# PGTNX01_teensy.net
KiCad netlist of a schematic drawn in EAGLE
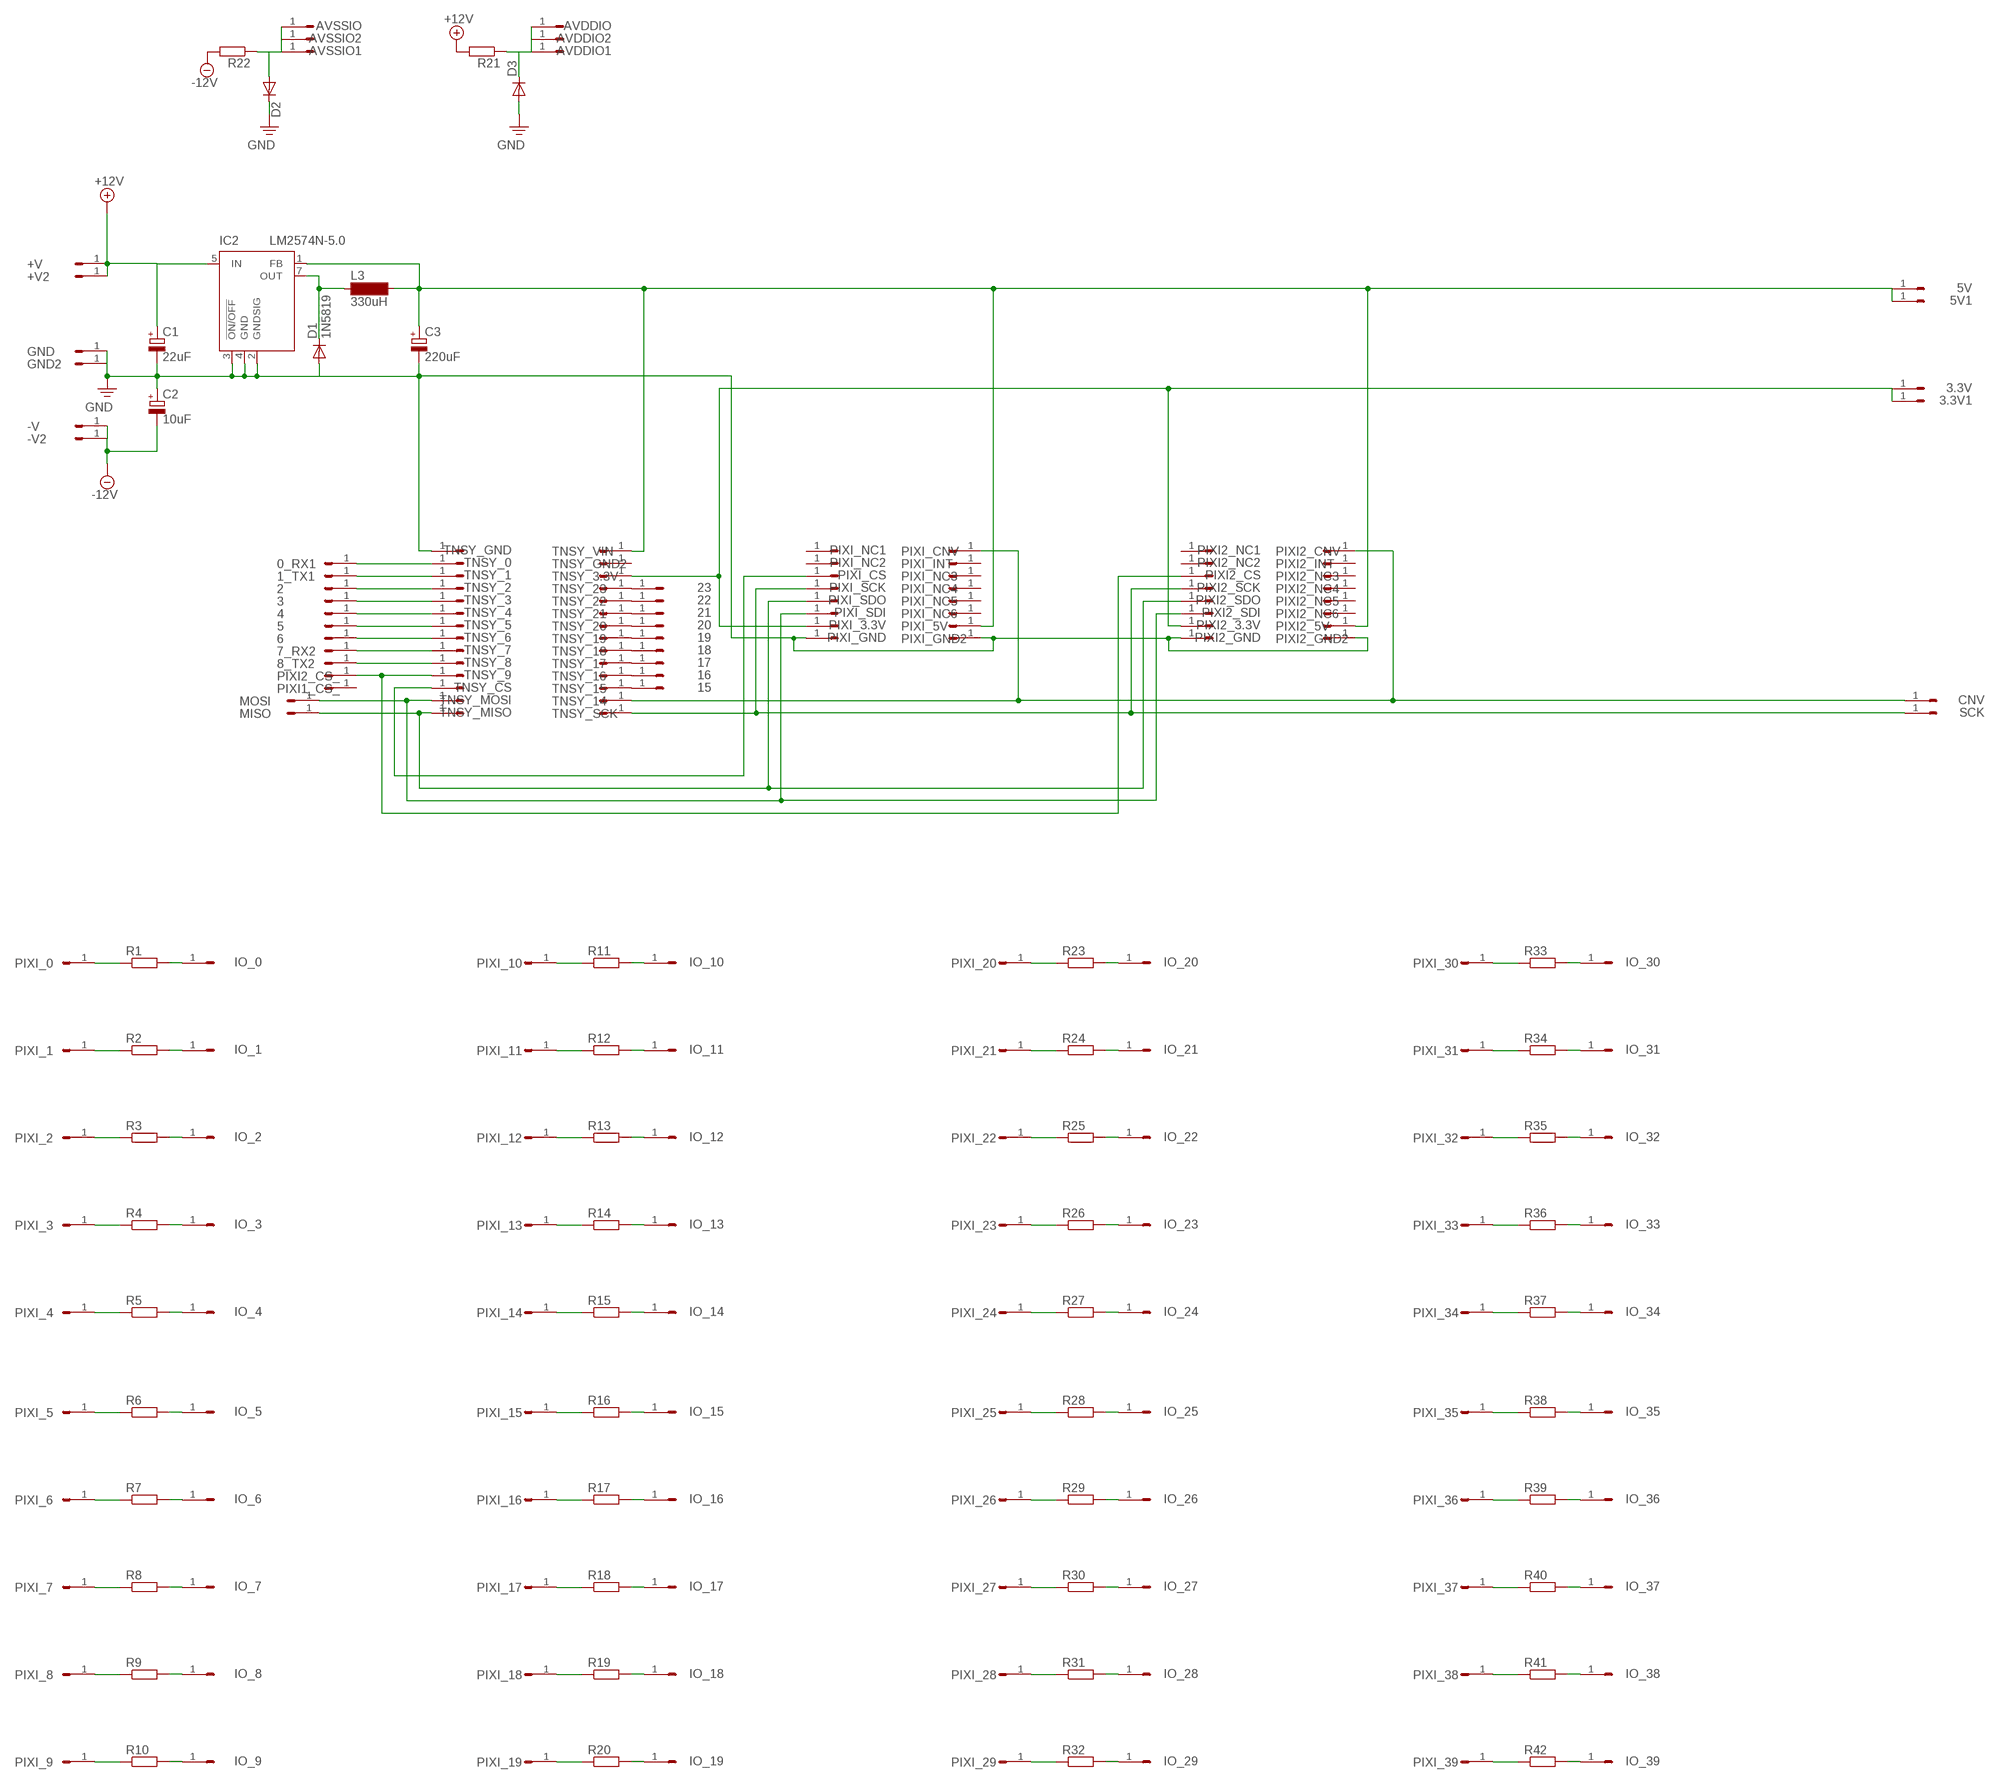
[diagram p0: schematic, sheet 1]

(export (version "E")
  (design (tool "Eeschema 10.0.6"))
  (components
    (comp (ref "+V")
      (value "HEADER/MALE/01")
      (footprint "eagle-import:HEADER_MALE_01")
      (fields (field (name "SPICEPREFIX") "X"))
      (libsource (lib "eagle-import") (part "HEADER/MALE/01"))
    )
    (comp (ref "+V2")
      (value "HEADER/MALE/01")
      (footprint "eagle-import:HEADER_MALE_01")
      (fields (field (name "SPICEPREFIX") "X"))
      (libsource (lib "eagle-import") (part "HEADER/MALE/01"))
    )
    (comp (ref "-V")
      (value "HEADER/MALE/01")
      (footprint "eagle-import:HEADER_MALE_01")
      (fields (field (name "SPICEPREFIX") "X"))
      (libsource (lib "eagle-import") (part "HEADER/MALE/01"))
    )
    (comp (ref "-V2")
      (value "HEADER/MALE/01")
      (footprint "eagle-import:HEADER_MALE_01")
      (fields (field (name "SPICEPREFIX") "X"))
      (libsource (lib "eagle-import") (part "HEADER/MALE/01"))
    )
    (comp (ref "0_RX1")
      (value "HEADER/MALE/01")
      (footprint "eagle-import:HEADER_MALE_01")
      (fields (field (name "SPICEPREFIX") "X"))
      (libsource (lib "eagle-import") (part "HEADER/MALE/01"))
    )
    (comp (ref "1_TX1")
      (value "HEADER/MALE/01")
      (footprint "eagle-import:HEADER_MALE_01")
      (fields (field (name "SPICEPREFIX") "X"))
      (libsource (lib "eagle-import") (part "HEADER/MALE/01"))
    )
    (comp (ref "2")
      (value "HEADER/MALE/01")
      (footprint "eagle-import:HEADER_MALE_01")
      (fields (field (name "SPICEPREFIX") "X"))
      (libsource (lib "eagle-import") (part "HEADER/MALE/01"))
    )
    (comp (ref "3")
      (value "HEADER/MALE/01")
      (footprint "eagle-import:HEADER_MALE_01")
      (fields (field (name "SPICEPREFIX") "X"))
      (libsource (lib "eagle-import") (part "HEADER/MALE/01"))
    )
    (comp (ref "3.3V")
      (value "HEADER/MALE/01")
      (footprint "eagle-import:HEADER_MALE_01")
      (fields (field (name "SPICEPREFIX") "X"))
      (libsource (lib "eagle-import") (part "HEADER/MALE/01"))
    )
    (comp (ref "3.3V1")
      (value "HEADER/MALE/01")
      (footprint "eagle-import:HEADER_MALE_01")
      (fields (field (name "SPICEPREFIX") "X"))
      (libsource (lib "eagle-import") (part "HEADER/MALE/01"))
    )
    (comp (ref "4")
      (value "HEADER/MALE/01")
      (footprint "eagle-import:HEADER_MALE_01")
      (fields (field (name "SPICEPREFIX") "X"))
      (libsource (lib "eagle-import") (part "HEADER/MALE/01"))
    )
    (comp (ref "5")
      (value "HEADER/MALE/01")
      (footprint "eagle-import:HEADER_MALE_01")
      (fields (field (name "SPICEPREFIX") "X"))
      (libsource (lib "eagle-import") (part "HEADER/MALE/01"))
    )
    (comp (ref "5V")
      (value "HEADER/MALE/01")
      (footprint "eagle-import:HEADER_MALE_01")
      (fields (field (name "SPICEPREFIX") "X"))
      (libsource (lib "eagle-import") (part "HEADER/MALE/01"))
    )
    (comp (ref "5V1")
      (value "HEADER/MALE/01")
      (footprint "eagle-import:HEADER_MALE_01")
      (fields (field (name "SPICEPREFIX") "X"))
      (libsource (lib "eagle-import") (part "HEADER/MALE/01"))
    )
    (comp (ref "6")
      (value "HEADER/MALE/01")
      (footprint "eagle-import:HEADER_MALE_01")
      (fields (field (name "SPICEPREFIX") "X"))
      (libsource (lib "eagle-import") (part "HEADER/MALE/01"))
    )
    (comp (ref "7_RX2")
      (value "HEADER/MALE/01")
      (footprint "eagle-import:HEADER_MALE_01")
      (fields (field (name "SPICEPREFIX") "X"))
      (libsource (lib "eagle-import") (part "HEADER/MALE/01"))
    )
    (comp (ref "8_TX2")
      (value "HEADER/MALE/01")
      (footprint "eagle-import:HEADER_MALE_01")
      (fields (field (name "SPICEPREFIX") "X"))
      (libsource (lib "eagle-import") (part "HEADER/MALE/01"))
    )
    (comp (ref "15")
      (value "HEADER/MALE/01")
      (footprint "eagle-import:HEADER_MALE_01")
      (fields (field (name "SPICEPREFIX") "X"))
      (libsource (lib "eagle-import") (part "HEADER/MALE/01"))
    )
    (comp (ref "16")
      (value "HEADER/MALE/01")
      (footprint "eagle-import:HEADER_MALE_01")
      (fields (field (name "SPICEPREFIX") "X"))
      (libsource (lib "eagle-import") (part "HEADER/MALE/01"))
    )
    (comp (ref "17")
      (value "HEADER/MALE/01")
      (footprint "eagle-import:HEADER_MALE_01")
      (fields (field (name "SPICEPREFIX") "X"))
      (libsource (lib "eagle-import") (part "HEADER/MALE/01"))
    )
    (comp (ref "18")
      (value "HEADER/MALE/01")
      (footprint "eagle-import:HEADER_MALE_01")
      (fields (field (name "SPICEPREFIX") "X"))
      (libsource (lib "eagle-import") (part "HEADER/MALE/01"))
    )
    (comp (ref "19")
      (value "HEADER/MALE/01")
      (footprint "eagle-import:HEADER_MALE_01")
      (fields (field (name "SPICEPREFIX") "X"))
      (libsource (lib "eagle-import") (part "HEADER/MALE/01"))
    )
    (comp (ref "20")
      (value "HEADER/MALE/01")
      (footprint "eagle-import:HEADER_MALE_01")
      (fields (field (name "SPICEPREFIX") "X"))
      (libsource (lib "eagle-import") (part "HEADER/MALE/01"))
    )
    (comp (ref "21")
      (value "HEADER/MALE/01")
      (footprint "eagle-import:HEADER_MALE_01")
      (fields (field (name "SPICEPREFIX") "X"))
      (libsource (lib "eagle-import") (part "HEADER/MALE/01"))
    )
    (comp (ref "22")
      (value "HEADER/MALE/01")
      (footprint "eagle-import:HEADER_MALE_01")
      (fields (field (name "SPICEPREFIX") "X"))
      (libsource (lib "eagle-import") (part "HEADER/MALE/01"))
    )
    (comp (ref "23")
      (value "HEADER/MALE/01")
      (footprint "eagle-import:HEADER_MALE_01")
      (fields (field (name "SPICEPREFIX") "X"))
      (libsource (lib "eagle-import") (part "HEADER/MALE/01"))
    )
    (comp (ref "AVDDIO")
      (value "HEADER/MALE/01")
      (footprint "eagle-import:HEADER_MALE_01")
      (fields (field (name "SPICEPREFIX") "X"))
      (libsource (lib "eagle-import") (part "HEADER/MALE/01"))
    )
    (comp (ref "AVDDIO1")
      (value "HEADER/MALE/01")
      (footprint "eagle-import:HEADER_MALE_01")
      (fields (field (name "SPICEPREFIX") "X"))
      (libsource (lib "eagle-import") (part "HEADER/MALE/01"))
    )
    (comp (ref "AVDDIO2")
      (value "HEADER/MALE/01")
      (footprint "eagle-import:HEADER_MALE_01")
      (fields (field (name "SPICEPREFIX") "X"))
      (libsource (lib "eagle-import") (part "HEADER/MALE/01"))
    )
    (comp (ref "AVSSIO")
      (value "HEADER/MALE/01")
      (footprint "eagle-import:HEADER_MALE_01")
      (fields (field (name "SPICEPREFIX") "X"))
      (libsource (lib "eagle-import") (part "HEADER/MALE/01"))
    )
    (comp (ref "AVSSIO1")
      (value "HEADER/MALE/01")
      (footprint "eagle-import:HEADER_MALE_01")
      (fields (field (name "SPICEPREFIX") "X"))
      (libsource (lib "eagle-import") (part "HEADER/MALE/01"))
    )
    (comp (ref "AVSSIO2")
      (value "HEADER/MALE/01")
      (footprint "eagle-import:HEADER_MALE_01")
      (fields (field (name "SPICEPREFIX") "X"))
      (libsource (lib "eagle-import") (part "HEADER/MALE/01"))
    )
    (comp (ref "C1")
      (value "22uF")
      (footprint "eagle-import:E5-10,5")
      (fields (field (name "SPICEPREFIX") "C"))
      (libsource (lib "eagle-import") (part "CAPACITOR/POLARIZEDE5-10.5"))
    )
    (comp (ref "C2")
      (value "10uF")
      (footprint "eagle-import:E2,5-6")
      (fields (field (name "SPICEPREFIX") "C"))
      (libsource (lib "eagle-import") (part "CAPACITOR/POLARIZEDE2.5-6"))
    )
    (comp (ref "C3")
      (value "220uF")
      (footprint "eagle-import:E2,5-6")
      (fields (field (name "SPICEPREFIX") "C"))
      (libsource (lib "eagle-import") (part "CAPACITOR/POLARIZEDE2.5-6"))
    )
    (comp (ref "CNV")
      (value "HEADER/MALE/01")
      (footprint "eagle-import:HEADER_MALE_01")
      (fields (field (name "SPICEPREFIX") "X"))
      (libsource (lib "eagle-import") (part "HEADER/MALE/01"))
    )
    (comp (ref "D1")
      (value "1N5819")
      (footprint "eagle-import:DO35-7")
      (libsource (lib "eagle-import") (part "1N4148DO35-7"))
    )
    (comp (ref "D2")
      (value "1N4148DO35-7")
      (footprint "eagle-import:DO35-7")
      (libsource (lib "eagle-import") (part "1N4148DO35-7"))
    )
    (comp (ref "D3")
      (value "1N4148DO35-7")
      (footprint "eagle-import:DO35-7")
      (libsource (lib "eagle-import") (part "1N4148DO35-7"))
    )
    (comp (ref "GND")
      (value "HEADER/MALE/01")
      (footprint "eagle-import:HEADER_MALE_01")
      (fields (field (name "SPICEPREFIX") "X"))
      (libsource (lib "eagle-import") (part "HEADER/MALE/01"))
    )
    (comp (ref "GND2")
      (value "HEADER/MALE/01")
      (footprint "eagle-import:HEADER_MALE_01")
      (fields (field (name "SPICEPREFIX") "X"))
      (libsource (lib "eagle-import") (part "HEADER/MALE/01"))
    )
    (comp (ref "IC2")
      (value "LM2574N-5.0")
      (footprint "eagle-import:DIL08")
      (libsource (lib "eagle-import") (part "LM2574?-N5.0"))
    )
    (comp (ref "IO_0")
      (value "HEADER/MALE/01")
      (footprint "eagle-import:HEADER_MALE_01")
      (fields (field (name "SPICEPREFIX") "X"))
      (libsource (lib "eagle-import") (part "HEADER/MALE/01"))
    )
    (comp (ref "IO_1")
      (value "HEADER/MALE/01")
      (footprint "eagle-import:HEADER_MALE_01")
      (fields (field (name "SPICEPREFIX") "X"))
      (libsource (lib "eagle-import") (part "HEADER/MALE/01"))
    )
    (comp (ref "IO_2")
      (value "HEADER/MALE/01")
      (footprint "eagle-import:HEADER_MALE_01")
      (fields (field (name "SPICEPREFIX") "X"))
      (libsource (lib "eagle-import") (part "HEADER/MALE/01"))
    )
    (comp (ref "IO_3")
      (value "HEADER/MALE/01")
      (footprint "eagle-import:HEADER_MALE_01")
      (fields (field (name "SPICEPREFIX") "X"))
      (libsource (lib "eagle-import") (part "HEADER/MALE/01"))
    )
    (comp (ref "IO_4")
      (value "HEADER/MALE/01")
      (footprint "eagle-import:HEADER_MALE_01")
      (fields (field (name "SPICEPREFIX") "X"))
      (libsource (lib "eagle-import") (part "HEADER/MALE/01"))
    )
    (comp (ref "IO_5")
      (value "HEADER/MALE/01")
      (footprint "eagle-import:HEADER_MALE_01")
      (fields (field (name "SPICEPREFIX") "X"))
      (libsource (lib "eagle-import") (part "HEADER/MALE/01"))
    )
    (comp (ref "IO_6")
      (value "HEADER/MALE/01")
      (footprint "eagle-import:HEADER_MALE_01")
      (fields (field (name "SPICEPREFIX") "X"))
      (libsource (lib "eagle-import") (part "HEADER/MALE/01"))
    )
    (comp (ref "IO_7")
      (value "HEADER/MALE/01")
      (footprint "eagle-import:HEADER_MALE_01")
      (fields (field (name "SPICEPREFIX") "X"))
      (libsource (lib "eagle-import") (part "HEADER/MALE/01"))
    )
    (comp (ref "IO_8")
      (value "HEADER/MALE/01")
      (footprint "eagle-import:HEADER_MALE_01")
      (fields (field (name "SPICEPREFIX") "X"))
      (libsource (lib "eagle-import") (part "HEADER/MALE/01"))
    )
    (comp (ref "IO_9")
      (value "HEADER/MALE/01")
      (footprint "eagle-import:HEADER_MALE_01")
      (fields (field (name "SPICEPREFIX") "X"))
      (libsource (lib "eagle-import") (part "HEADER/MALE/01"))
    )
    (comp (ref "IO_10")
      (value "HEADER/MALE/01")
      (footprint "eagle-import:HEADER_MALE_01")
      (fields (field (name "SPICEPREFIX") "X"))
      (libsource (lib "eagle-import") (part "HEADER/MALE/01"))
    )
    (comp (ref "IO_11")
      (value "HEADER/MALE/01")
      (footprint "eagle-import:HEADER_MALE_01")
      (fields (field (name "SPICEPREFIX") "X"))
      (libsource (lib "eagle-import") (part "HEADER/MALE/01"))
    )
    (comp (ref "IO_12")
      (value "HEADER/MALE/01")
      (footprint "eagle-import:HEADER_MALE_01")
      (fields (field (name "SPICEPREFIX") "X"))
      (libsource (lib "eagle-import") (part "HEADER/MALE/01"))
    )
    (comp (ref "IO_13")
      (value "HEADER/MALE/01")
      (footprint "eagle-import:HEADER_MALE_01")
      (fields (field (name "SPICEPREFIX") "X"))
      (libsource (lib "eagle-import") (part "HEADER/MALE/01"))
    )
    (comp (ref "IO_14")
      (value "HEADER/MALE/01")
      (footprint "eagle-import:HEADER_MALE_01")
      (fields (field (name "SPICEPREFIX") "X"))
      (libsource (lib "eagle-import") (part "HEADER/MALE/01"))
    )
    (comp (ref "IO_15")
      (value "HEADER/MALE/01")
      (footprint "eagle-import:HEADER_MALE_01")
      (fields (field (name "SPICEPREFIX") "X"))
      (libsource (lib "eagle-import") (part "HEADER/MALE/01"))
    )
    (comp (ref "IO_16")
      (value "HEADER/MALE/01")
      (footprint "eagle-import:HEADER_MALE_01")
      (fields (field (name "SPICEPREFIX") "X"))
      (libsource (lib "eagle-import") (part "HEADER/MALE/01"))
    )
    (comp (ref "IO_17")
      (value "HEADER/MALE/01")
      (footprint "eagle-import:HEADER_MALE_01")
      (fields (field (name "SPICEPREFIX") "X"))
      (libsource (lib "eagle-import") (part "HEADER/MALE/01"))
    )
    (comp (ref "IO_18")
      (value "HEADER/MALE/01")
      (footprint "eagle-import:HEADER_MALE_01")
      (fields (field (name "SPICEPREFIX") "X"))
      (libsource (lib "eagle-import") (part "HEADER/MALE/01"))
    )
    (comp (ref "IO_19")
      (value "HEADER/MALE/01")
      (footprint "eagle-import:HEADER_MALE_01")
      (fields (field (name "SPICEPREFIX") "X"))
      (libsource (lib "eagle-import") (part "HEADER/MALE/01"))
    )
    (comp (ref "IO_20")
      (value "HEADER/MALE/01")
      (footprint "eagle-import:HEADER_MALE_01")
      (fields (field (name "SPICEPREFIX") "X"))
      (libsource (lib "eagle-import") (part "HEADER/MALE/01"))
    )
    (comp (ref "IO_21")
      (value "HEADER/MALE/01")
      (footprint "eagle-import:HEADER_MALE_01")
      (fields (field (name "SPICEPREFIX") "X"))
      (libsource (lib "eagle-import") (part "HEADER/MALE/01"))
    )
    (comp (ref "IO_22")
      (value "HEADER/MALE/01")
      (footprint "eagle-import:HEADER_MALE_01")
      (fields (field (name "SPICEPREFIX") "X"))
      (libsource (lib "eagle-import") (part "HEADER/MALE/01"))
    )
    (comp (ref "IO_23")
      (value "HEADER/MALE/01")
      (footprint "eagle-import:HEADER_MALE_01")
      (fields (field (name "SPICEPREFIX") "X"))
      (libsource (lib "eagle-import") (part "HEADER/MALE/01"))
    )
    (comp (ref "IO_24")
      (value "HEADER/MALE/01")
      (footprint "eagle-import:HEADER_MALE_01")
      (fields (field (name "SPICEPREFIX") "X"))
      (libsource (lib "eagle-import") (part "HEADER/MALE/01"))
    )
    (comp (ref "IO_25")
      (value "HEADER/MALE/01")
      (footprint "eagle-import:HEADER_MALE_01")
      (fields (field (name "SPICEPREFIX") "X"))
      (libsource (lib "eagle-import") (part "HEADER/MALE/01"))
    )
    (comp (ref "IO_26")
      (value "HEADER/MALE/01")
      (footprint "eagle-import:HEADER_MALE_01")
      (fields (field (name "SPICEPREFIX") "X"))
      (libsource (lib "eagle-import") (part "HEADER/MALE/01"))
    )
    (comp (ref "IO_27")
      (value "HEADER/MALE/01")
      (footprint "eagle-import:HEADER_MALE_01")
      (fields (field (name "SPICEPREFIX") "X"))
      (libsource (lib "eagle-import") (part "HEADER/MALE/01"))
    )
    (comp (ref "IO_28")
      (value "HEADER/MALE/01")
      (footprint "eagle-import:HEADER_MALE_01")
      (fields (field (name "SPICEPREFIX") "X"))
      (libsource (lib "eagle-import") (part "HEADER/MALE/01"))
    )
    (comp (ref "IO_29")
      (value "HEADER/MALE/01")
      (footprint "eagle-import:HEADER_MALE_01")
      (fields (field (name "SPICEPREFIX") "X"))
      (libsource (lib "eagle-import") (part "HEADER/MALE/01"))
    )
    (comp (ref "IO_30")
      (value "HEADER/MALE/01")
      (footprint "eagle-import:HEADER_MALE_01")
      (fields (field (name "SPICEPREFIX") "X"))
      (libsource (lib "eagle-import") (part "HEADER/MALE/01"))
    )
    (comp (ref "IO_31")
      (value "HEADER/MALE/01")
      (footprint "eagle-import:HEADER_MALE_01")
      (fields (field (name "SPICEPREFIX") "X"))
      (libsource (lib "eagle-import") (part "HEADER/MALE/01"))
    )
    (comp (ref "IO_32")
      (value "HEADER/MALE/01")
      (footprint "eagle-import:HEADER_MALE_01")
      (fields (field (name "SPICEPREFIX") "X"))
      (libsource (lib "eagle-import") (part "HEADER/MALE/01"))
    )
    (comp (ref "IO_33")
      (value "HEADER/MALE/01")
      (footprint "eagle-import:HEADER_MALE_01")
      (fields (field (name "SPICEPREFIX") "X"))
      (libsource (lib "eagle-import") (part "HEADER/MALE/01"))
    )
    (comp (ref "IO_34")
      (value "HEADER/MALE/01")
      (footprint "eagle-import:HEADER_MALE_01")
      (fields (field (name "SPICEPREFIX") "X"))
      (libsource (lib "eagle-import") (part "HEADER/MALE/01"))
    )
    (comp (ref "IO_35")
      (value "HEADER/MALE/01")
      (footprint "eagle-import:HEADER_MALE_01")
      (fields (field (name "SPICEPREFIX") "X"))
      (libsource (lib "eagle-import") (part "HEADER/MALE/01"))
    )
    (comp (ref "IO_36")
      (value "HEADER/MALE/01")
      (footprint "eagle-import:HEADER_MALE_01")
      (fields (field (name "SPICEPREFIX") "X"))
      (libsource (lib "eagle-import") (part "HEADER/MALE/01"))
    )
    (comp (ref "IO_37")
      (value "HEADER/MALE/01")
      (footprint "eagle-import:HEADER_MALE_01")
      (fields (field (name "SPICEPREFIX") "X"))
      (libsource (lib "eagle-import") (part "HEADER/MALE/01"))
    )
    (comp (ref "IO_38")
      (value "HEADER/MALE/01")
      (footprint "eagle-import:HEADER_MALE_01")
      (fields (field (name "SPICEPREFIX") "X"))
      (libsource (lib "eagle-import") (part "HEADER/MALE/01"))
    )
    (comp (ref "IO_39")
      (value "HEADER/MALE/01")
      (footprint "eagle-import:HEADER_MALE_01")
      (fields (field (name "SPICEPREFIX") "X"))
      (libsource (lib "eagle-import") (part "HEADER/MALE/01"))
    )
    (comp (ref "L3")
      (value "330uH")
      (footprint "eagle-import:BS11")
      (libsource (lib "eagle-import") (part "BS11"))
    )
    (comp (ref "MISO")
      (value "HEADER/MALE/01")
      (footprint "eagle-import:HEADER_MALE_01")
      (fields (field (name "SPICEPREFIX") "X"))
      (libsource (lib "eagle-import") (part "HEADER/MALE/01"))
    )
    (comp (ref "MOSI")
      (value "HEADER/MALE/01")
      (footprint "eagle-import:HEADER_MALE_01")
      (fields (field (name "SPICEPREFIX") "X"))
      (libsource (lib "eagle-import") (part "HEADER/MALE/01"))
    )
    (comp (ref "PIXI1_CS_")
      (value "HEADER/MALE/01")
      (footprint "eagle-import:HEADER_MALE_01")
      (fields (field (name "SPICEPREFIX") "X"))
      (libsource (lib "eagle-import") (part "HEADER/MALE/01"))
    )
    (comp (ref "PIXI2_3.3V")
      (value "HEADER/MALE/01")
      (footprint "eagle-import:HEADER_MALE_01")
      (fields (field (name "SPICEPREFIX") "X"))
      (libsource (lib "eagle-import") (part "HEADER/MALE/01"))
    )
    (comp (ref "PIXI2_5V")
      (value "HEADER/MALE/01")
      (footprint "eagle-import:HEADER_MALE_01")
      (fields (field (name "SPICEPREFIX") "X"))
      (libsource (lib "eagle-import") (part "HEADER/MALE/01"))
    )
    (comp (ref "PIXI2_CNV")
      (value "HEADER/MALE/01")
      (footprint "eagle-import:HEADER_MALE_01")
      (fields (field (name "SPICEPREFIX") "X"))
      (libsource (lib "eagle-import") (part "HEADER/MALE/01"))
    )
    (comp (ref "PIXI2_CS")
      (value "HEADER/MALE/01")
      (footprint "eagle-import:HEADER_MALE_01")
      (fields (field (name "SPICEPREFIX") "X"))
      (libsource (lib "eagle-import") (part "HEADER/MALE/01"))
    )
    (comp (ref "PIXI2_CS_")
      (value "HEADER/MALE/01")
      (footprint "eagle-import:HEADER_MALE_01")
      (fields (field (name "SPICEPREFIX") "X"))
      (libsource (lib "eagle-import") (part "HEADER/MALE/01"))
    )
    (comp (ref "PIXI2_GND")
      (value "HEADER/MALE/01")
      (footprint "eagle-import:HEADER_MALE_01")
      (fields (field (name "SPICEPREFIX") "X"))
      (libsource (lib "eagle-import") (part "HEADER/MALE/01"))
    )
    (comp (ref "PIXI2_GND2")
      (value "HEADER/MALE/01")
      (footprint "eagle-import:HEADER_MALE_01")
      (fields (field (name "SPICEPREFIX") "X"))
      (libsource (lib "eagle-import") (part "HEADER/MALE/01"))
    )
    (comp (ref "PIXI2_INT")
      (value "HEADER/MALE/01")
      (footprint "eagle-import:HEADER_MALE_01")
      (fields (field (name "SPICEPREFIX") "X"))
      (libsource (lib "eagle-import") (part "HEADER/MALE/01"))
    )
    (comp (ref "PIXI2_NC1")
      (value "HEADER/MALE/01")
      (footprint "eagle-import:HEADER_MALE_01")
      (fields (field (name "SPICEPREFIX") "X"))
      (libsource (lib "eagle-import") (part "HEADER/MALE/01"))
    )
    (comp (ref "PIXI2_NC2")
      (value "HEADER/MALE/01")
      (footprint "eagle-import:HEADER_MALE_01")
      (fields (field (name "SPICEPREFIX") "X"))
      (libsource (lib "eagle-import") (part "HEADER/MALE/01"))
    )
    (comp (ref "PIXI2_NC3")
      (value "HEADER/MALE/01")
      (footprint "eagle-import:HEADER_MALE_01")
      (fields (field (name "SPICEPREFIX") "X"))
      (libsource (lib "eagle-import") (part "HEADER/MALE/01"))
    )
    (comp (ref "PIXI2_NC4")
      (value "HEADER/MALE/01")
      (footprint "eagle-import:HEADER_MALE_01")
      (fields (field (name "SPICEPREFIX") "X"))
      (libsource (lib "eagle-import") (part "HEADER/MALE/01"))
    )
    (comp (ref "PIXI2_NC5")
      (value "HEADER/MALE/01")
      (footprint "eagle-import:HEADER_MALE_01")
      (fields (field (name "SPICEPREFIX") "X"))
      (libsource (lib "eagle-import") (part "HEADER/MALE/01"))
    )
    (comp (ref "PIXI2_NC6")
      (value "HEADER/MALE/01")
      (footprint "eagle-import:HEADER_MALE_01")
      (fields (field (name "SPICEPREFIX") "X"))
      (libsource (lib "eagle-import") (part "HEADER/MALE/01"))
    )
    (comp (ref "PIXI2_SCK")
      (value "HEADER/MALE/01")
      (footprint "eagle-import:HEADER_MALE_01")
      (fields (field (name "SPICEPREFIX") "X"))
      (libsource (lib "eagle-import") (part "HEADER/MALE/01"))
    )
    (comp (ref "PIXI2_SDI")
      (value "HEADER/MALE/01")
      (footprint "eagle-import:HEADER_MALE_01")
      (fields (field (name "SPICEPREFIX") "X"))
      (libsource (lib "eagle-import") (part "HEADER/MALE/01"))
    )
    (comp (ref "PIXI2_SDO")
      (value "HEADER/MALE/01")
      (footprint "eagle-import:HEADER_MALE_01")
      (fields (field (name "SPICEPREFIX") "X"))
      (libsource (lib "eagle-import") (part "HEADER/MALE/01"))
    )
    (comp (ref "PIXI_0")
      (value "HEADER/MALE/01")
      (footprint "eagle-import:HEADER_MALE_01")
      (fields (field (name "SPICEPREFIX") "X"))
      (libsource (lib "eagle-import") (part "HEADER/MALE/01"))
    )
    (comp (ref "PIXI_1")
      (value "HEADER/MALE/01")
      (footprint "eagle-import:HEADER_MALE_01")
      (fields (field (name "SPICEPREFIX") "X"))
      (libsource (lib "eagle-import") (part "HEADER/MALE/01"))
    )
    (comp (ref "PIXI_2")
      (value "HEADER/MALE/01")
      (footprint "eagle-import:HEADER_MALE_01")
      (fields (field (name "SPICEPREFIX") "X"))
      (libsource (lib "eagle-import") (part "HEADER/MALE/01"))
    )
    (comp (ref "PIXI_3")
      (value "HEADER/MALE/01")
      (footprint "eagle-import:HEADER_MALE_01")
      (fields (field (name "SPICEPREFIX") "X"))
      (libsource (lib "eagle-import") (part "HEADER/MALE/01"))
    )
    (comp (ref "PIXI_3.3V")
      (value "HEADER/MALE/01")
      (footprint "eagle-import:HEADER_MALE_01")
      (fields (field (name "SPICEPREFIX") "X"))
      (libsource (lib "eagle-import") (part "HEADER/MALE/01"))
    )
    (comp (ref "PIXI_4")
      (value "HEADER/MALE/01")
      (footprint "eagle-import:HEADER_MALE_01")
      (fields (field (name "SPICEPREFIX") "X"))
      (libsource (lib "eagle-import") (part "HEADER/MALE/01"))
    )
    (comp (ref "PIXI_5")
      (value "HEADER/MALE/01")
      (footprint "eagle-import:HEADER_MALE_01")
      (fields (field (name "SPICEPREFIX") "X"))
      (libsource (lib "eagle-import") (part "HEADER/MALE/01"))
    )
    (comp (ref "PIXI_5V")
      (value "HEADER/MALE/01")
      (footprint "eagle-import:HEADER_MALE_01")
      (fields (field (name "SPICEPREFIX") "X"))
      (libsource (lib "eagle-import") (part "HEADER/MALE/01"))
    )
    (comp (ref "PIXI_6")
      (value "HEADER/MALE/01")
      (footprint "eagle-import:HEADER_MALE_01")
      (fields (field (name "SPICEPREFIX") "X"))
      (libsource (lib "eagle-import") (part "HEADER/MALE/01"))
    )
    (comp (ref "PIXI_7")
      (value "HEADER/MALE/01")
      (footprint "eagle-import:HEADER_MALE_01")
      (fields (field (name "SPICEPREFIX") "X"))
      (libsource (lib "eagle-import") (part "HEADER/MALE/01"))
    )
    (comp (ref "PIXI_8")
      (value "HEADER/MALE/01")
      (footprint "eagle-import:HEADER_MALE_01")
      (fields (field (name "SPICEPREFIX") "X"))
      (libsource (lib "eagle-import") (part "HEADER/MALE/01"))
    )
    (comp (ref "PIXI_9")
      (value "HEADER/MALE/01")
      (footprint "eagle-import:HEADER_MALE_01")
      (fields (field (name "SPICEPREFIX") "X"))
      (libsource (lib "eagle-import") (part "HEADER/MALE/01"))
    )
    (comp (ref "PIXI_10")
      (value "HEADER/MALE/01")
      (footprint "eagle-import:HEADER_MALE_01")
      (fields (field (name "SPICEPREFIX") "X"))
      (libsource (lib "eagle-import") (part "HEADER/MALE/01"))
    )
    (comp (ref "PIXI_11")
      (value "HEADER/MALE/01")
      (footprint "eagle-import:HEADER_MALE_01")
      (fields (field (name "SPICEPREFIX") "X"))
      (libsource (lib "eagle-import") (part "HEADER/MALE/01"))
    )
    (comp (ref "PIXI_12")
      (value "HEADER/MALE/01")
      (footprint "eagle-import:HEADER_MALE_01")
      (fields (field (name "SPICEPREFIX") "X"))
      (libsource (lib "eagle-import") (part "HEADER/MALE/01"))
    )
    (comp (ref "PIXI_13")
      (value "HEADER/MALE/01")
      (footprint "eagle-import:HEADER_MALE_01")
      (fields (field (name "SPICEPREFIX") "X"))
      (libsource (lib "eagle-import") (part "HEADER/MALE/01"))
    )
    (comp (ref "PIXI_14")
      (value "HEADER/MALE/01")
      (footprint "eagle-import:HEADER_MALE_01")
      (fields (field (name "SPICEPREFIX") "X"))
      (libsource (lib "eagle-import") (part "HEADER/MALE/01"))
    )
    (comp (ref "PIXI_15")
      (value "HEADER/MALE/01")
      (footprint "eagle-import:HEADER_MALE_01")
      (fields (field (name "SPICEPREFIX") "X"))
      (libsource (lib "eagle-import") (part "HEADER/MALE/01"))
    )
    (comp (ref "PIXI_16")
      (value "HEADER/MALE/01")
      (footprint "eagle-import:HEADER_MALE_01")
      (fields (field (name "SPICEPREFIX") "X"))
      (libsource (lib "eagle-import") (part "HEADER/MALE/01"))
    )
    (comp (ref "PIXI_17")
      (value "HEADER/MALE/01")
      (footprint "eagle-import:HEADER_MALE_01")
      (fields (field (name "SPICEPREFIX") "X"))
      (libsource (lib "eagle-import") (part "HEADER/MALE/01"))
    )
    (comp (ref "PIXI_18")
      (value "HEADER/MALE/01")
      (footprint "eagle-import:HEADER_MALE_01")
      (fields (field (name "SPICEPREFIX") "X"))
      (libsource (lib "eagle-import") (part "HEADER/MALE/01"))
    )
    (comp (ref "PIXI_19")
      (value "HEADER/MALE/01")
      (footprint "eagle-import:HEADER_MALE_01")
      (fields (field (name "SPICEPREFIX") "X"))
      (libsource (lib "eagle-import") (part "HEADER/MALE/01"))
    )
    (comp (ref "PIXI_20")
      (value "HEADER/MALE/01")
      (footprint "eagle-import:HEADER_MALE_01")
      (fields (field (name "SPICEPREFIX") "X"))
      (libsource (lib "eagle-import") (part "HEADER/MALE/01"))
    )
    (comp (ref "PIXI_21")
      (value "HEADER/MALE/01")
      (footprint "eagle-import:HEADER_MALE_01")
      (fields (field (name "SPICEPREFIX") "X"))
      (libsource (lib "eagle-import") (part "HEADER/MALE/01"))
    )
    (comp (ref "PIXI_22")
      (value "HEADER/MALE/01")
      (footprint "eagle-import:HEADER_MALE_01")
      (fields (field (name "SPICEPREFIX") "X"))
      (libsource (lib "eagle-import") (part "HEADER/MALE/01"))
    )
    (comp (ref "PIXI_23")
      (value "HEADER/MALE/01")
      (footprint "eagle-import:HEADER_MALE_01")
      (fields (field (name "SPICEPREFIX") "X"))
      (libsource (lib "eagle-import") (part "HEADER/MALE/01"))
    )
    (comp (ref "PIXI_24")
      (value "HEADER/MALE/01")
      (footprint "eagle-import:HEADER_MALE_01")
      (fields (field (name "SPICEPREFIX") "X"))
      (libsource (lib "eagle-import") (part "HEADER/MALE/01"))
    )
    (comp (ref "PIXI_25")
      (value "HEADER/MALE/01")
      (footprint "eagle-import:HEADER_MALE_01")
      (fields (field (name "SPICEPREFIX") "X"))
      (libsource (lib "eagle-import") (part "HEADER/MALE/01"))
    )
    (comp (ref "PIXI_26")
      (value "HEADER/MALE/01")
      (footprint "eagle-import:HEADER_MALE_01")
      (fields (field (name "SPICEPREFIX") "X"))
      (libsource (lib "eagle-import") (part "HEADER/MALE/01"))
    )
    (comp (ref "PIXI_27")
      (value "HEADER/MALE/01")
      (footprint "eagle-import:HEADER_MALE_01")
      (fields (field (name "SPICEPREFIX") "X"))
      (libsource (lib "eagle-import") (part "HEADER/MALE/01"))
    )
    (comp (ref "PIXI_28")
      (value "HEADER/MALE/01")
      (footprint "eagle-import:HEADER_MALE_01")
      (fields (field (name "SPICEPREFIX") "X"))
      (libsource (lib "eagle-import") (part "HEADER/MALE/01"))
    )
    (comp (ref "PIXI_29")
      (value "HEADER/MALE/01")
      (footprint "eagle-import:HEADER_MALE_01")
      (fields (field (name "SPICEPREFIX") "X"))
      (libsource (lib "eagle-import") (part "HEADER/MALE/01"))
    )
    (comp (ref "PIXI_30")
      (value "HEADER/MALE/01")
      (footprint "eagle-import:HEADER_MALE_01")
      (fields (field (name "SPICEPREFIX") "X"))
      (libsource (lib "eagle-import") (part "HEADER/MALE/01"))
    )
    (comp (ref "PIXI_31")
      (value "HEADER/MALE/01")
      (footprint "eagle-import:HEADER_MALE_01")
      (fields (field (name "SPICEPREFIX") "X"))
      (libsource (lib "eagle-import") (part "HEADER/MALE/01"))
    )
    (comp (ref "PIXI_32")
      (value "HEADER/MALE/01")
      (footprint "eagle-import:HEADER_MALE_01")
      (fields (field (name "SPICEPREFIX") "X"))
      (libsource (lib "eagle-import") (part "HEADER/MALE/01"))
    )
    (comp (ref "PIXI_33")
      (value "HEADER/MALE/01")
      (footprint "eagle-import:HEADER_MALE_01")
      (fields (field (name "SPICEPREFIX") "X"))
      (libsource (lib "eagle-import") (part "HEADER/MALE/01"))
    )
    (comp (ref "PIXI_34")
      (value "HEADER/MALE/01")
      (footprint "eagle-import:HEADER_MALE_01")
      (fields (field (name "SPICEPREFIX") "X"))
      (libsource (lib "eagle-import") (part "HEADER/MALE/01"))
    )
    (comp (ref "PIXI_35")
      (value "HEADER/MALE/01")
      (footprint "eagle-import:HEADER_MALE_01")
      (fields (field (name "SPICEPREFIX") "X"))
      (libsource (lib "eagle-import") (part "HEADER/MALE/01"))
    )
    (comp (ref "PIXI_36")
      (value "HEADER/MALE/01")
      (footprint "eagle-import:HEADER_MALE_01")
      (fields (field (name "SPICEPREFIX") "X"))
      (libsource (lib "eagle-import") (part "HEADER/MALE/01"))
    )
    (comp (ref "PIXI_37")
      (value "HEADER/MALE/01")
      (footprint "eagle-import:HEADER_MALE_01")
      (fields (field (name "SPICEPREFIX") "X"))
      (libsource (lib "eagle-import") (part "HEADER/MALE/01"))
    )
    (comp (ref "PIXI_38")
      (value "HEADER/MALE/01")
      (footprint "eagle-import:HEADER_MALE_01")
      (fields (field (name "SPICEPREFIX") "X"))
      (libsource (lib "eagle-import") (part "HEADER/MALE/01"))
    )
    (comp (ref "PIXI_39")
      (value "HEADER/MALE/01")
      (footprint "eagle-import:HEADER_MALE_01")
      (fields (field (name "SPICEPREFIX") "X"))
      (libsource (lib "eagle-import") (part "HEADER/MALE/01"))
    )
    (comp (ref "PIXI_CNV")
      (value "HEADER/MALE/01")
      (footprint "eagle-import:HEADER_MALE_01")
      (fields (field (name "SPICEPREFIX") "X"))
      (libsource (lib "eagle-import") (part "HEADER/MALE/01"))
    )
    (comp (ref "PIXI_CS")
      (value "HEADER/MALE/01")
      (footprint "eagle-import:HEADER_MALE_01")
      (fields (field (name "SPICEPREFIX") "X"))
      (libsource (lib "eagle-import") (part "HEADER/MALE/01"))
    )
    (comp (ref "PIXI_GND")
      (value "HEADER/MALE/01")
      (footprint "eagle-import:HEADER_MALE_01")
      (fields (field (name "SPICEPREFIX") "X"))
      (libsource (lib "eagle-import") (part "HEADER/MALE/01"))
    )
    (comp (ref "PIXI_GND2")
      (value "HEADER/MALE/01")
      (footprint "eagle-import:HEADER_MALE_01")
      (fields (field (name "SPICEPREFIX") "X"))
      (libsource (lib "eagle-import") (part "HEADER/MALE/01"))
    )
    (comp (ref "PIXI_INT")
      (value "HEADER/MALE/01")
      (footprint "eagle-import:HEADER_MALE_01")
      (fields (field (name "SPICEPREFIX") "X"))
      (libsource (lib "eagle-import") (part "HEADER/MALE/01"))
    )
    (comp (ref "PIXI_NC1")
      (value "HEADER/MALE/01")
      (footprint "eagle-import:HEADER_MALE_01")
      (fields (field (name "SPICEPREFIX") "X"))
      (libsource (lib "eagle-import") (part "HEADER/MALE/01"))
    )
    (comp (ref "PIXI_NC2")
      (value "HEADER/MALE/01")
      (footprint "eagle-import:HEADER_MALE_01")
      (fields (field (name "SPICEPREFIX") "X"))
      (libsource (lib "eagle-import") (part "HEADER/MALE/01"))
    )
    (comp (ref "PIXI_NC3")
      (value "HEADER/MALE/01")
      (footprint "eagle-import:HEADER_MALE_01")
      (fields (field (name "SPICEPREFIX") "X"))
      (libsource (lib "eagle-import") (part "HEADER/MALE/01"))
    )
    (comp (ref "PIXI_NC4")
      (value "HEADER/MALE/01")
      (footprint "eagle-import:HEADER_MALE_01")
      (fields (field (name "SPICEPREFIX") "X"))
      (libsource (lib "eagle-import") (part "HEADER/MALE/01"))
    )
    (comp (ref "PIXI_NC5")
      (value "HEADER/MALE/01")
      (footprint "eagle-import:HEADER_MALE_01")
      (fields (field (name "SPICEPREFIX") "X"))
      (libsource (lib "eagle-import") (part "HEADER/MALE/01"))
    )
    (comp (ref "PIXI_NC6")
      (value "HEADER/MALE/01")
      (footprint "eagle-import:HEADER_MALE_01")
      (fields (field (name "SPICEPREFIX") "X"))
      (libsource (lib "eagle-import") (part "HEADER/MALE/01"))
    )
    (comp (ref "PIXI_SCK")
      (value "HEADER/MALE/01")
      (footprint "eagle-import:HEADER_MALE_01")
      (fields (field (name "SPICEPREFIX") "X"))
      (libsource (lib "eagle-import") (part "HEADER/MALE/01"))
    )
    (comp (ref "PIXI_SDI")
      (value "HEADER/MALE/01")
      (footprint "eagle-import:HEADER_MALE_01")
      (fields (field (name "SPICEPREFIX") "X"))
      (libsource (lib "eagle-import") (part "HEADER/MALE/01"))
    )
    (comp (ref "PIXI_SDO")
      (value "HEADER/MALE/01")
      (footprint "eagle-import:HEADER_MALE_01")
      (fields (field (name "SPICEPREFIX") "X"))
      (libsource (lib "eagle-import") (part "HEADER/MALE/01"))
    )
    (comp (ref "R1")
      (value "RESISTORRESISTOR/UPRIGHT/7.5")
      (footprint "eagle-import:RESISTOR_7.5")
      (libsource (lib "eagle-import") (part "RESISTORRESISTOR/UPRIGHT/7.5"))
    )
    (comp (ref "R2")
      (value "RESISTORRESISTOR/UPRIGHT/7.5")
      (footprint "eagle-import:RESISTOR_7.5")
      (libsource (lib "eagle-import") (part "RESISTORRESISTOR/UPRIGHT/7.5"))
    )
    (comp (ref "R3")
      (value "RESISTORRESISTOR/UPRIGHT/7.5")
      (footprint "eagle-import:RESISTOR_7.5")
      (libsource (lib "eagle-import") (part "RESISTORRESISTOR/UPRIGHT/7.5"))
    )
    (comp (ref "R4")
      (value "RESISTORRESISTOR/UPRIGHT/7.5")
      (footprint "eagle-import:RESISTOR_7.5")
      (libsource (lib "eagle-import") (part "RESISTORRESISTOR/UPRIGHT/7.5"))
    )
    (comp (ref "R5")
      (value "RESISTORRESISTOR/UPRIGHT/7.5")
      (footprint "eagle-import:RESISTOR_7.5")
      (libsource (lib "eagle-import") (part "RESISTORRESISTOR/UPRIGHT/7.5"))
    )
    (comp (ref "R6")
      (value "RESISTORRESISTOR/UPRIGHT/7.5")
      (footprint "eagle-import:RESISTOR_7.5")
      (libsource (lib "eagle-import") (part "RESISTORRESISTOR/UPRIGHT/7.5"))
    )
    (comp (ref "R7")
      (value "RESISTORRESISTOR/UPRIGHT/7.5")
      (footprint "eagle-import:RESISTOR_7.5")
      (libsource (lib "eagle-import") (part "RESISTORRESISTOR/UPRIGHT/7.5"))
    )
    (comp (ref "R8")
      (value "RESISTORRESISTOR/UPRIGHT/7.5")
      (footprint "eagle-import:RESISTOR_7.5")
      (libsource (lib "eagle-import") (part "RESISTORRESISTOR/UPRIGHT/7.5"))
    )
    (comp (ref "R9")
      (value "RESISTORRESISTOR/UPRIGHT/7.5")
      (footprint "eagle-import:RESISTOR_7.5")
      (libsource (lib "eagle-import") (part "RESISTORRESISTOR/UPRIGHT/7.5"))
    )
    (comp (ref "R10")
      (value "RESISTORRESISTOR/UPRIGHT/7.5")
      (footprint "eagle-import:RESISTOR_7.5")
      (libsource (lib "eagle-import") (part "RESISTORRESISTOR/UPRIGHT/7.5"))
    )
    (comp (ref "R11")
      (value "RESISTORRESISTOR/UPRIGHT/7.5")
      (footprint "eagle-import:RESISTOR_7.5")
      (libsource (lib "eagle-import") (part "RESISTORRESISTOR/UPRIGHT/7.5"))
    )
    (comp (ref "R12")
      (value "RESISTORRESISTOR/UPRIGHT/7.5")
      (footprint "eagle-import:RESISTOR_7.5")
      (libsource (lib "eagle-import") (part "RESISTORRESISTOR/UPRIGHT/7.5"))
    )
    (comp (ref "R13")
      (value "RESISTORRESISTOR/UPRIGHT/7.5")
      (footprint "eagle-import:RESISTOR_7.5")
      (libsource (lib "eagle-import") (part "RESISTORRESISTOR/UPRIGHT/7.5"))
    )
    (comp (ref "R14")
      (value "RESISTORRESISTOR/UPRIGHT/7.5")
      (footprint "eagle-import:RESISTOR_7.5")
      (libsource (lib "eagle-import") (part "RESISTORRESISTOR/UPRIGHT/7.5"))
    )
    (comp (ref "R15")
      (value "RESISTORRESISTOR/UPRIGHT/7.5")
      (footprint "eagle-import:RESISTOR_7.5")
      (libsource (lib "eagle-import") (part "RESISTORRESISTOR/UPRIGHT/7.5"))
    )
    (comp (ref "R16")
      (value "RESISTORRESISTOR/UPRIGHT/7.5")
      (footprint "eagle-import:RESISTOR_7.5")
      (libsource (lib "eagle-import") (part "RESISTORRESISTOR/UPRIGHT/7.5"))
    )
    (comp (ref "R17")
      (value "RESISTORRESISTOR/UPRIGHT/7.5")
      (footprint "eagle-import:RESISTOR_7.5")
      (libsource (lib "eagle-import") (part "RESISTORRESISTOR/UPRIGHT/7.5"))
    )
    (comp (ref "R18")
      (value "RESISTORRESISTOR/UPRIGHT/7.5")
      (footprint "eagle-import:RESISTOR_7.5")
      (libsource (lib "eagle-import") (part "RESISTORRESISTOR/UPRIGHT/7.5"))
    )
    (comp (ref "R19")
      (value "RESISTORRESISTOR/UPRIGHT/7.5")
      (footprint "eagle-import:RESISTOR_7.5")
      (libsource (lib "eagle-import") (part "RESISTORRESISTOR/UPRIGHT/7.5"))
    )
    (comp (ref "R20")
      (value "RESISTORRESISTOR/UPRIGHT/7.5")
      (footprint "eagle-import:RESISTOR_7.5")
      (libsource (lib "eagle-import") (part "RESISTORRESISTOR/UPRIGHT/7.5"))
    )
    (comp (ref "R21")
      (value "RESISTORRESISTOR/UPRIGHT/7.5")
      (footprint "eagle-import:RESISTOR_7.5")
      (libsource (lib "eagle-import") (part "RESISTORRESISTOR/UPRIGHT/7.5"))
    )
    (comp (ref "R22")
      (value "RESISTORRESISTOR/UPRIGHT/7.5")
      (footprint "eagle-import:RESISTOR_7.5")
      (libsource (lib "eagle-import") (part "RESISTORRESISTOR/UPRIGHT/7.5"))
    )
    (comp (ref "R23")
      (value "RESISTORRESISTOR/UPRIGHT/7.5")
      (footprint "eagle-import:RESISTOR_7.5")
      (libsource (lib "eagle-import") (part "RESISTORRESISTOR/UPRIGHT/7.5"))
    )
    (comp (ref "R24")
      (value "RESISTORRESISTOR/UPRIGHT/7.5")
      (footprint "eagle-import:RESISTOR_7.5")
      (libsource (lib "eagle-import") (part "RESISTORRESISTOR/UPRIGHT/7.5"))
    )
    (comp (ref "R25")
      (value "RESISTORRESISTOR/UPRIGHT/7.5")
      (footprint "eagle-import:RESISTOR_7.5")
      (libsource (lib "eagle-import") (part "RESISTORRESISTOR/UPRIGHT/7.5"))
    )
    (comp (ref "R26")
      (value "RESISTORRESISTOR/UPRIGHT/7.5")
      (footprint "eagle-import:RESISTOR_7.5")
      (libsource (lib "eagle-import") (part "RESISTORRESISTOR/UPRIGHT/7.5"))
    )
    (comp (ref "R27")
      (value "RESISTORRESISTOR/UPRIGHT/7.5")
      (footprint "eagle-import:RESISTOR_7.5")
      (libsource (lib "eagle-import") (part "RESISTORRESISTOR/UPRIGHT/7.5"))
    )
    (comp (ref "R28")
      (value "RESISTORRESISTOR/UPRIGHT/7.5")
      (footprint "eagle-import:RESISTOR_7.5")
      (libsource (lib "eagle-import") (part "RESISTORRESISTOR/UPRIGHT/7.5"))
    )
    (comp (ref "R29")
      (value "RESISTORRESISTOR/UPRIGHT/7.5")
      (footprint "eagle-import:RESISTOR_7.5")
      (libsource (lib "eagle-import") (part "RESISTORRESISTOR/UPRIGHT/7.5"))
    )
    (comp (ref "R30")
      (value "RESISTORRESISTOR/UPRIGHT/7.5")
      (footprint "eagle-import:RESISTOR_7.5")
      (libsource (lib "eagle-import") (part "RESISTORRESISTOR/UPRIGHT/7.5"))
    )
    (comp (ref "R31")
      (value "RESISTORRESISTOR/UPRIGHT/7.5")
      (footprint "eagle-import:RESISTOR_7.5")
      (libsource (lib "eagle-import") (part "RESISTORRESISTOR/UPRIGHT/7.5"))
    )
    (comp (ref "R32")
      (value "RESISTORRESISTOR/UPRIGHT/7.5")
      (footprint "eagle-import:RESISTOR_7.5")
      (libsource (lib "eagle-import") (part "RESISTORRESISTOR/UPRIGHT/7.5"))
    )
    (comp (ref "R33")
      (value "RESISTORRESISTOR/UPRIGHT/7.5")
      (footprint "eagle-import:RESISTOR_7.5")
      (libsource (lib "eagle-import") (part "RESISTORRESISTOR/UPRIGHT/7.5"))
    )
    (comp (ref "R34")
      (value "RESISTORRESISTOR/UPRIGHT/7.5")
      (footprint "eagle-import:RESISTOR_7.5")
      (libsource (lib "eagle-import") (part "RESISTORRESISTOR/UPRIGHT/7.5"))
    )
    (comp (ref "R35")
      (value "RESISTORRESISTOR/UPRIGHT/7.5")
      (footprint "eagle-import:RESISTOR_7.5")
      (libsource (lib "eagle-import") (part "RESISTORRESISTOR/UPRIGHT/7.5"))
    )
    (comp (ref "R36")
      (value "RESISTORRESISTOR/UPRIGHT/7.5")
      (footprint "eagle-import:RESISTOR_7.5")
      (libsource (lib "eagle-import") (part "RESISTORRESISTOR/UPRIGHT/7.5"))
    )
    (comp (ref "R37")
      (value "RESISTORRESISTOR/UPRIGHT/7.5")
      (footprint "eagle-import:RESISTOR_7.5")
      (libsource (lib "eagle-import") (part "RESISTORRESISTOR/UPRIGHT/7.5"))
    )
    (comp (ref "R38")
      (value "RESISTORRESISTOR/UPRIGHT/7.5")
      (footprint "eagle-import:RESISTOR_7.5")
      (libsource (lib "eagle-import") (part "RESISTORRESISTOR/UPRIGHT/7.5"))
    )
    (comp (ref "R39")
      (value "RESISTORRESISTOR/UPRIGHT/7.5")
      (footprint "eagle-import:RESISTOR_7.5")
      (libsource (lib "eagle-import") (part "RESISTORRESISTOR/UPRIGHT/7.5"))
    )
    (comp (ref "R40")
      (value "RESISTORRESISTOR/UPRIGHT/7.5")
      (footprint "eagle-import:RESISTOR_7.5")
      (libsource (lib "eagle-import") (part "RESISTORRESISTOR/UPRIGHT/7.5"))
    )
    (comp (ref "R41")
      (value "RESISTORRESISTOR/UPRIGHT/7.5")
      (footprint "eagle-import:RESISTOR_7.5")
      (libsource (lib "eagle-import") (part "RESISTORRESISTOR/UPRIGHT/7.5"))
    )
    (comp (ref "R42")
      (value "RESISTORRESISTOR/UPRIGHT/7.5")
      (footprint "eagle-import:RESISTOR_7.5")
      (libsource (lib "eagle-import") (part "RESISTORRESISTOR/UPRIGHT/7.5"))
    )
    (comp (ref "SCK")
      (value "HEADER/MALE/01")
      (footprint "eagle-import:HEADER_MALE_01")
      (fields (field (name "SPICEPREFIX") "X"))
      (libsource (lib "eagle-import") (part "HEADER/MALE/01"))
    )
    (comp (ref "TNSY_0")
      (value "HEADER/MALE/01")
      (footprint "eagle-import:HEADER_MALE_01")
      (fields (field (name "SPICEPREFIX") "X"))
      (libsource (lib "eagle-import") (part "HEADER/MALE/01"))
    )
    (comp (ref "TNSY_1")
      (value "HEADER/MALE/01")
      (footprint "eagle-import:HEADER_MALE_01")
      (fields (field (name "SPICEPREFIX") "X"))
      (libsource (lib "eagle-import") (part "HEADER/MALE/01"))
    )
    (comp (ref "TNSY_2")
      (value "HEADER/MALE/01")
      (footprint "eagle-import:HEADER_MALE_01")
      (fields (field (name "SPICEPREFIX") "X"))
      (libsource (lib "eagle-import") (part "HEADER/MALE/01"))
    )
    (comp (ref "TNSY_3")
      (value "HEADER/MALE/01")
      (footprint "eagle-import:HEADER_MALE_01")
      (fields (field (name "SPICEPREFIX") "X"))
      (libsource (lib "eagle-import") (part "HEADER/MALE/01"))
    )
    (comp (ref "TNSY_3.3V")
      (value "HEADER/MALE/01")
      (footprint "eagle-import:HEADER_MALE_01")
      (fields (field (name "SPICEPREFIX") "X"))
      (libsource (lib "eagle-import") (part "HEADER/MALE/01"))
    )
    (comp (ref "TNSY_4")
      (value "HEADER/MALE/01")
      (footprint "eagle-import:HEADER_MALE_01")
      (fields (field (name "SPICEPREFIX") "X"))
      (libsource (lib "eagle-import") (part "HEADER/MALE/01"))
    )
    (comp (ref "TNSY_5")
      (value "HEADER/MALE/01")
      (footprint "eagle-import:HEADER_MALE_01")
      (fields (field (name "SPICEPREFIX") "X"))
      (libsource (lib "eagle-import") (part "HEADER/MALE/01"))
    )
    (comp (ref "TNSY_6")
      (value "HEADER/MALE/01")
      (footprint "eagle-import:HEADER_MALE_01")
      (fields (field (name "SPICEPREFIX") "X"))
      (libsource (lib "eagle-import") (part "HEADER/MALE/01"))
    )
    (comp (ref "TNSY_7")
      (value "HEADER/MALE/01")
      (footprint "eagle-import:HEADER_MALE_01")
      (fields (field (name "SPICEPREFIX") "X"))
      (libsource (lib "eagle-import") (part "HEADER/MALE/01"))
    )
    (comp (ref "TNSY_8")
      (value "HEADER/MALE/01")
      (footprint "eagle-import:HEADER_MALE_01")
      (fields (field (name "SPICEPREFIX") "X"))
      (libsource (lib "eagle-import") (part "HEADER/MALE/01"))
    )
    (comp (ref "TNSY_9")
      (value "HEADER/MALE/01")
      (footprint "eagle-import:HEADER_MALE_01")
      (fields (field (name "SPICEPREFIX") "X"))
      (libsource (lib "eagle-import") (part "HEADER/MALE/01"))
    )
    (comp (ref "TNSY_14")
      (value "HEADER/MALE/01")
      (footprint "eagle-import:HEADER_MALE_01")
      (fields (field (name "SPICEPREFIX") "X"))
      (libsource (lib "eagle-import") (part "HEADER/MALE/01"))
    )
    (comp (ref "TNSY_15")
      (value "HEADER/MALE/01")
      (footprint "eagle-import:HEADER_MALE_01")
      (fields (field (name "SPICEPREFIX") "X"))
      (libsource (lib "eagle-import") (part "HEADER/MALE/01"))
    )
    (comp (ref "TNSY_16")
      (value "HEADER/MALE/01")
      (footprint "eagle-import:HEADER_MALE_01")
      (fields (field (name "SPICEPREFIX") "X"))
      (libsource (lib "eagle-import") (part "HEADER/MALE/01"))
    )
    (comp (ref "TNSY_17")
      (value "HEADER/MALE/01")
      (footprint "eagle-import:HEADER_MALE_01")
      (fields (field (name "SPICEPREFIX") "X"))
      (libsource (lib "eagle-import") (part "HEADER/MALE/01"))
    )
    (comp (ref "TNSY_18")
      (value "HEADER/MALE/01")
      (footprint "eagle-import:HEADER_MALE_01")
      (fields (field (name "SPICEPREFIX") "X"))
      (libsource (lib "eagle-import") (part "HEADER/MALE/01"))
    )
    (comp (ref "TNSY_19")
      (value "HEADER/MALE/01")
      (footprint "eagle-import:HEADER_MALE_01")
      (fields (field (name "SPICEPREFIX") "X"))
      (libsource (lib "eagle-import") (part "HEADER/MALE/01"))
    )
    (comp (ref "TNSY_20")
      (value "HEADER/MALE/01")
      (footprint "eagle-import:HEADER_MALE_01")
      (fields (field (name "SPICEPREFIX") "X"))
      (libsource (lib "eagle-import") (part "HEADER/MALE/01"))
    )
    (comp (ref "TNSY_21")
      (value "HEADER/MALE/01")
      (footprint "eagle-import:HEADER_MALE_01")
      (fields (field (name "SPICEPREFIX") "X"))
      (libsource (lib "eagle-import") (part "HEADER/MALE/01"))
    )
    (comp (ref "TNSY_22")
      (value "HEADER/MALE/01")
      (footprint "eagle-import:HEADER_MALE_01")
      (fields (field (name "SPICEPREFIX") "X"))
      (libsource (lib "eagle-import") (part "HEADER/MALE/01"))
    )
    (comp (ref "TNSY_23")
      (value "HEADER/MALE/01")
      (footprint "eagle-import:HEADER_MALE_01")
      (fields (field (name "SPICEPREFIX") "X"))
      (libsource (lib "eagle-import") (part "HEADER/MALE/01"))
    )
    (comp (ref "TNSY_CS")
      (value "HEADER/MALE/01")
      (footprint "eagle-import:HEADER_MALE_01")
      (fields (field (name "SPICEPREFIX") "X"))
      (libsource (lib "eagle-import") (part "HEADER/MALE/01"))
    )
    (comp (ref "TNSY_GND")
      (value "HEADER/MALE/01")
      (footprint "eagle-import:HEADER_MALE_01")
      (fields (field (name "SPICEPREFIX") "X"))
      (libsource (lib "eagle-import") (part "HEADER/MALE/01"))
    )
    (comp (ref "TNSY_GND2")
      (value "HEADER/MALE/01")
      (footprint "eagle-import:HEADER_MALE_01")
      (fields (field (name "SPICEPREFIX") "X"))
      (libsource (lib "eagle-import") (part "HEADER/MALE/01"))
    )
    (comp (ref "TNSY_MISO")
      (value "HEADER/MALE/01")
      (footprint "eagle-import:HEADER_MALE_01")
      (fields (field (name "SPICEPREFIX") "X"))
      (libsource (lib "eagle-import") (part "HEADER/MALE/01"))
    )
    (comp (ref "TNSY_MOSI")
      (value "HEADER/MALE/01")
      (footprint "eagle-import:HEADER_MALE_01")
      (fields (field (name "SPICEPREFIX") "X"))
      (libsource (lib "eagle-import") (part "HEADER/MALE/01"))
    )
    (comp (ref "TNSY_SCK")
      (value "HEADER/MALE/01")
      (footprint "eagle-import:HEADER_MALE_01")
      (fields (field (name "SPICEPREFIX") "X"))
      (libsource (lib "eagle-import") (part "HEADER/MALE/01"))
    )
    (comp (ref "TNSY_VIN")
      (value "HEADER/MALE/01")
      (footprint "eagle-import:HEADER_MALE_01")
      (fields (field (name "SPICEPREFIX") "X"))
      (libsource (lib "eagle-import") (part "HEADER/MALE/01"))
    )
  )
  (nets
    (net (code "1") (name "+12V") (class "Default")
      (node (ref "+V") (pin "1") (pinfunction "3_1") (pintype "passive"))
      (node (ref "+V2") (pin "1") (pinfunction "3_1") (pintype "passive"))
      (node (ref "C1") (pin "+") (pinfunction "+_+") (pintype "passive"))
      (node (ref "IC2") (pin "5") (pinfunction "IN_5") (pintype "input"))
      (node (ref "R21") (pin "2") (pinfunction "2_2") (pintype "passive"))
    )
    (net (code "2") (name "-12V") (class "Default")
      (node (ref "-V") (pin "1") (pinfunction "3_1") (pintype "passive"))
      (node (ref "-V2") (pin "1") (pinfunction "3_1") (pintype "passive"))
      (node (ref "C2") (pin "-") (pinfunction "-_-") (pintype "passive"))
      (node (ref "R22") (pin "2") (pinfunction "2_2") (pintype "passive"))
    )
    (net (code "3") (name "GND") (class "Default")
      (node (ref "C1") (pin "-") (pinfunction "-_-") (pintype "passive"))
      (node (ref "C2") (pin "+") (pinfunction "+_+") (pintype "passive"))
      (node (ref "C3") (pin "-") (pinfunction "-_-") (pintype "passive"))
      (node (ref "D1") (pin "A") (pinfunction "A_A") (pintype "passive"))
      (node (ref "D2") (pin "C") (pinfunction "C_C") (pintype "passive"))
      (node (ref "D3") (pin "A") (pinfunction "A_A") (pintype "passive"))
      (node (ref "GND") (pin "1") (pinfunction "3_1") (pintype "passive"))
      (node (ref "GND2") (pin "1") (pinfunction "3_1") (pintype "passive"))
      (node (ref "IC2") (pin "2") (pinfunction "GNDSIG_2") (pintype "input"))
      (node (ref "IC2") (pin "3") (pinfunction "~{ON/OFF}_3") (pintype "input"))
      (node (ref "IC2") (pin "4") (pinfunction "GND_4") (pintype "power_in"))
      (node (ref "PIXI2_GND") (pin "1") (pinfunction "3_1") (pintype "passive"))
      (node (ref "PIXI2_GND2") (pin "1") (pinfunction "3_1") (pintype "passive"))
      (node (ref "PIXI_GND") (pin "1") (pinfunction "3_1") (pintype "passive"))
      (node (ref "PIXI_GND2") (pin "1") (pinfunction "3_1") (pintype "passive"))
      (node (ref "TNSY_GND") (pin "1") (pinfunction "3_1") (pintype "passive"))
    )
    (net (code "4") (name "Net-(0_RX1-3)") (class "Default")
      (node (ref "0_RX1") (pin "1") (pinfunction "3_1") (pintype "passive"))
      (node (ref "TNSY_0") (pin "1") (pinfunction "3_1") (pintype "passive"))
    )
    (net (code "5") (name "Net-(1_TX1-3)") (class "Default")
      (node (ref "1_TX1") (pin "1") (pinfunction "3_1") (pintype "passive"))
      (node (ref "TNSY_1") (pin "1") (pinfunction "3_1") (pintype "passive"))
    )
    (net (code "6") (name "Net-(2-3)") (class "Default")
      (node (ref "2") (pin "1") (pinfunction "3_1") (pintype "passive"))
      (node (ref "TNSY_2") (pin "1") (pinfunction "3_1") (pintype "passive"))
    )
    (net (code "7") (name "Net-(3-3)") (class "Default")
      (node (ref "3") (pin "1") (pinfunction "3_1") (pintype "passive"))
      (node (ref "TNSY_3") (pin "1") (pinfunction "3_1") (pintype "passive"))
    )
    (net (code "8") (name "Net-(3.3V-3)") (class "Default")
      (node (ref "3.3V") (pin "1") (pinfunction "3_1") (pintype "passive"))
      (node (ref "3.3V1") (pin "1") (pinfunction "3_1") (pintype "passive"))
      (node (ref "PIXI2_3.3V") (pin "1") (pinfunction "3_1") (pintype "passive"))
      (node (ref "PIXI_3.3V") (pin "1") (pinfunction "3_1") (pintype "passive"))
      (node (ref "TNSY_3.3V") (pin "1") (pinfunction "3_1") (pintype "passive"))
    )
    (net (code "9") (name "Net-(4-3)") (class "Default")
      (node (ref "4") (pin "1") (pinfunction "3_1") (pintype "passive"))
      (node (ref "TNSY_4") (pin "1") (pinfunction "3_1") (pintype "passive"))
    )
    (net (code "10") (name "Net-(5-3)") (class "Default")
      (node (ref "5") (pin "1") (pinfunction "3_1") (pintype "passive"))
      (node (ref "TNSY_5") (pin "1") (pinfunction "3_1") (pintype "passive"))
    )
    (net (code "11") (name "Net-(5V-3)") (class "Default")
      (node (ref "5V") (pin "1") (pinfunction "3_1") (pintype "passive"))
      (node (ref "5V1") (pin "1") (pinfunction "3_1") (pintype "passive"))
      (node (ref "C3") (pin "+") (pinfunction "+_+") (pintype "passive"))
      (node (ref "IC2") (pin "1") (pinfunction "FB_1") (pintype "input"))
      (node (ref "L3") (pin "2") (pinfunction "2_2") (pintype "passive"))
      (node (ref "PIXI2_5V") (pin "1") (pinfunction "3_1") (pintype "passive"))
      (node (ref "PIXI_5V") (pin "1") (pinfunction "3_1") (pintype "passive"))
      (node (ref "TNSY_VIN") (pin "1") (pinfunction "3_1") (pintype "passive"))
    )
    (net (code "12") (name "Net-(6-3)") (class "Default")
      (node (ref "6") (pin "1") (pinfunction "3_1") (pintype "passive"))
      (node (ref "TNSY_6") (pin "1") (pinfunction "3_1") (pintype "passive"))
    )
    (net (code "13") (name "Net-(7_RX2-3)") (class "Default")
      (node (ref "7_RX2") (pin "1") (pinfunction "3_1") (pintype "passive"))
      (node (ref "TNSY_7") (pin "1") (pinfunction "3_1") (pintype "passive"))
    )
    (net (code "14") (name "Net-(8_TX2-3)") (class "Default")
      (node (ref "8_TX2") (pin "1") (pinfunction "3_1") (pintype "passive"))
      (node (ref "TNSY_8") (pin "1") (pinfunction "3_1") (pintype "passive"))
    )
    (net (code "15") (name "Net-(15-3)") (class "Default")
      (node (ref "15") (pin "1") (pinfunction "3_1") (pintype "passive"))
      (node (ref "TNSY_15") (pin "1") (pinfunction "3_1") (pintype "passive"))
    )
    (net (code "16") (name "Net-(16-3)") (class "Default")
      (node (ref "16") (pin "1") (pinfunction "3_1") (pintype "passive"))
      (node (ref "TNSY_16") (pin "1") (pinfunction "3_1") (pintype "passive"))
    )
    (net (code "17") (name "Net-(17-3)") (class "Default")
      (node (ref "17") (pin "1") (pinfunction "3_1") (pintype "passive"))
      (node (ref "TNSY_17") (pin "1") (pinfunction "3_1") (pintype "passive"))
    )
    (net (code "18") (name "Net-(18-3)") (class "Default")
      (node (ref "18") (pin "1") (pinfunction "3_1") (pintype "passive"))
      (node (ref "TNSY_18") (pin "1") (pinfunction "3_1") (pintype "passive"))
    )
    (net (code "19") (name "Net-(19-3)") (class "Default")
      (node (ref "19") (pin "1") (pinfunction "3_1") (pintype "passive"))
      (node (ref "TNSY_19") (pin "1") (pinfunction "3_1") (pintype "passive"))
    )
    (net (code "20") (name "Net-(20-3)") (class "Default")
      (node (ref "20") (pin "1") (pinfunction "3_1") (pintype "passive"))
      (node (ref "TNSY_20") (pin "1") (pinfunction "3_1") (pintype "passive"))
    )
    (net (code "21") (name "Net-(21-3)") (class "Default")
      (node (ref "21") (pin "1") (pinfunction "3_1") (pintype "passive"))
      (node (ref "TNSY_21") (pin "1") (pinfunction "3_1") (pintype "passive"))
    )
    (net (code "22") (name "Net-(22-3)") (class "Default")
      (node (ref "22") (pin "1") (pinfunction "3_1") (pintype "passive"))
      (node (ref "TNSY_22") (pin "1") (pinfunction "3_1") (pintype "passive"))
    )
    (net (code "23") (name "Net-(23-3)") (class "Default")
      (node (ref "23") (pin "1") (pinfunction "3_1") (pintype "passive"))
      (node (ref "TNSY_23") (pin "1") (pinfunction "3_1") (pintype "passive"))
    )
    (net (code "24") (name "Net-(AVDDIO-3)") (class "Default")
      (node (ref "AVDDIO") (pin "1") (pinfunction "3_1") (pintype "passive"))
      (node (ref "AVDDIO1") (pin "1") (pinfunction "3_1") (pintype "passive"))
      (node (ref "AVDDIO2") (pin "1") (pinfunction "3_1") (pintype "passive"))
      (node (ref "D3") (pin "C") (pinfunction "C_C") (pintype "passive"))
      (node (ref "R21") (pin "1") (pinfunction "1_1") (pintype "passive"))
    )
    (net (code "25") (name "Net-(AVSSIO-3)") (class "Default")
      (node (ref "AVSSIO") (pin "1") (pinfunction "3_1") (pintype "passive"))
      (node (ref "AVSSIO1") (pin "1") (pinfunction "3_1") (pintype "passive"))
      (node (ref "AVSSIO2") (pin "1") (pinfunction "3_1") (pintype "passive"))
      (node (ref "D2") (pin "A") (pinfunction "A_A") (pintype "passive"))
      (node (ref "R22") (pin "1") (pinfunction "1_1") (pintype "passive"))
    )
    (net (code "26") (name "Net-(CNV-3)") (class "Default")
      (node (ref "CNV") (pin "1") (pinfunction "3_1") (pintype "passive"))
      (node (ref "PIXI2_CNV") (pin "1") (pinfunction "3_1") (pintype "passive"))
      (node (ref "PIXI_CNV") (pin "1") (pinfunction "3_1") (pintype "passive"))
      (node (ref "TNSY_14") (pin "1") (pinfunction "3_1") (pintype "passive"))
    )
    (net (code "27") (name "Net-(IC2-OUT)") (class "Default")
      (node (ref "D1") (pin "C") (pinfunction "C_C") (pintype "passive"))
      (node (ref "IC2") (pin "7") (pinfunction "OUT_7") (pintype "passive"))
      (node (ref "L3") (pin "1") (pinfunction "1_1") (pintype "passive"))
    )
    (net (code "28") (name "Net-(IO_0-3)") (class "Default")
      (node (ref "IO_0") (pin "1") (pinfunction "3_1") (pintype "passive"))
      (node (ref "R1") (pin "2") (pinfunction "2_2") (pintype "passive"))
    )
    (net (code "29") (name "Net-(IO_1-3)") (class "Default")
      (node (ref "IO_1") (pin "1") (pinfunction "3_1") (pintype "passive"))
      (node (ref "R2") (pin "2") (pinfunction "2_2") (pintype "passive"))
    )
    (net (code "30") (name "Net-(IO_2-3)") (class "Default")
      (node (ref "IO_2") (pin "1") (pinfunction "3_1") (pintype "passive"))
      (node (ref "R3") (pin "2") (pinfunction "2_2") (pintype "passive"))
    )
    (net (code "31") (name "Net-(IO_3-3)") (class "Default")
      (node (ref "IO_3") (pin "1") (pinfunction "3_1") (pintype "passive"))
      (node (ref "R4") (pin "2") (pinfunction "2_2") (pintype "passive"))
    )
    (net (code "32") (name "Net-(IO_4-3)") (class "Default")
      (node (ref "IO_4") (pin "1") (pinfunction "3_1") (pintype "passive"))
      (node (ref "R5") (pin "2") (pinfunction "2_2") (pintype "passive"))
    )
    (net (code "33") (name "Net-(IO_5-3)") (class "Default")
      (node (ref "IO_5") (pin "1") (pinfunction "3_1") (pintype "passive"))
      (node (ref "R6") (pin "2") (pinfunction "2_2") (pintype "passive"))
    )
    (net (code "34") (name "Net-(IO_6-3)") (class "Default")
      (node (ref "IO_6") (pin "1") (pinfunction "3_1") (pintype "passive"))
      (node (ref "R7") (pin "2") (pinfunction "2_2") (pintype "passive"))
    )
    (net (code "35") (name "Net-(IO_7-3)") (class "Default")
      (node (ref "IO_7") (pin "1") (pinfunction "3_1") (pintype "passive"))
      (node (ref "R8") (pin "2") (pinfunction "2_2") (pintype "passive"))
    )
    (net (code "36") (name "Net-(IO_8-3)") (class "Default")
      (node (ref "IO_8") (pin "1") (pinfunction "3_1") (pintype "passive"))
      (node (ref "R9") (pin "2") (pinfunction "2_2") (pintype "passive"))
    )
    (net (code "37") (name "Net-(IO_9-3)") (class "Default")
      (node (ref "IO_9") (pin "1") (pinfunction "3_1") (pintype "passive"))
      (node (ref "R10") (pin "2") (pinfunction "2_2") (pintype "passive"))
    )
    (net (code "38") (name "Net-(IO_10-3)") (class "Default")
      (node (ref "IO_10") (pin "1") (pinfunction "3_1") (pintype "passive"))
      (node (ref "R11") (pin "2") (pinfunction "2_2") (pintype "passive"))
    )
    (net (code "39") (name "Net-(IO_11-3)") (class "Default")
      (node (ref "IO_11") (pin "1") (pinfunction "3_1") (pintype "passive"))
      (node (ref "R12") (pin "2") (pinfunction "2_2") (pintype "passive"))
    )
    (net (code "40") (name "Net-(IO_12-3)") (class "Default")
      (node (ref "IO_12") (pin "1") (pinfunction "3_1") (pintype "passive"))
      (node (ref "R13") (pin "2") (pinfunction "2_2") (pintype "passive"))
    )
    (net (code "41") (name "Net-(IO_13-3)") (class "Default")
      (node (ref "IO_13") (pin "1") (pinfunction "3_1") (pintype "passive"))
      (node (ref "R14") (pin "2") (pinfunction "2_2") (pintype "passive"))
    )
    (net (code "42") (name "Net-(IO_14-3)") (class "Default")
      (node (ref "IO_14") (pin "1") (pinfunction "3_1") (pintype "passive"))
      (node (ref "R15") (pin "2") (pinfunction "2_2") (pintype "passive"))
    )
    (net (code "43") (name "Net-(IO_15-3)") (class "Default")
      (node (ref "IO_15") (pin "1") (pinfunction "3_1") (pintype "passive"))
      (node (ref "R16") (pin "2") (pinfunction "2_2") (pintype "passive"))
    )
    (net (code "44") (name "Net-(IO_16-3)") (class "Default")
      (node (ref "IO_16") (pin "1") (pinfunction "3_1") (pintype "passive"))
      (node (ref "R17") (pin "2") (pinfunction "2_2") (pintype "passive"))
    )
    (net (code "45") (name "Net-(IO_17-3)") (class "Default")
      (node (ref "IO_17") (pin "1") (pinfunction "3_1") (pintype "passive"))
      (node (ref "R18") (pin "2") (pinfunction "2_2") (pintype "passive"))
    )
    (net (code "46") (name "Net-(IO_18-3)") (class "Default")
      (node (ref "IO_18") (pin "1") (pinfunction "3_1") (pintype "passive"))
      (node (ref "R19") (pin "2") (pinfunction "2_2") (pintype "passive"))
    )
    (net (code "47") (name "Net-(IO_19-3)") (class "Default")
      (node (ref "IO_19") (pin "1") (pinfunction "3_1") (pintype "passive"))
      (node (ref "R20") (pin "2") (pinfunction "2_2") (pintype "passive"))
    )
    (net (code "48") (name "Net-(IO_20-3)") (class "Default")
      (node (ref "IO_20") (pin "1") (pinfunction "3_1") (pintype "passive"))
      (node (ref "R23") (pin "2") (pinfunction "2_2") (pintype "passive"))
    )
    (net (code "49") (name "Net-(IO_21-3)") (class "Default")
      (node (ref "IO_21") (pin "1") (pinfunction "3_1") (pintype "passive"))
      (node (ref "R24") (pin "2") (pinfunction "2_2") (pintype "passive"))
    )
    (net (code "50") (name "Net-(IO_22-3)") (class "Default")
      (node (ref "IO_22") (pin "1") (pinfunction "3_1") (pintype "passive"))
      (node (ref "R25") (pin "2") (pinfunction "2_2") (pintype "passive"))
    )
    (net (code "51") (name "Net-(IO_23-3)") (class "Default")
      (node (ref "IO_23") (pin "1") (pinfunction "3_1") (pintype "passive"))
      (node (ref "R26") (pin "2") (pinfunction "2_2") (pintype "passive"))
    )
    (net (code "52") (name "Net-(IO_24-3)") (class "Default")
      (node (ref "IO_24") (pin "1") (pinfunction "3_1") (pintype "passive"))
      (node (ref "R27") (pin "2") (pinfunction "2_2") (pintype "passive"))
    )
    (net (code "53") (name "Net-(IO_25-3)") (class "Default")
      (node (ref "IO_25") (pin "1") (pinfunction "3_1") (pintype "passive"))
      (node (ref "R28") (pin "2") (pinfunction "2_2") (pintype "passive"))
    )
    (net (code "54") (name "Net-(IO_26-3)") (class "Default")
      (node (ref "IO_26") (pin "1") (pinfunction "3_1") (pintype "passive"))
      (node (ref "R29") (pin "2") (pinfunction "2_2") (pintype "passive"))
    )
    (net (code "55") (name "Net-(IO_27-3)") (class "Default")
      (node (ref "IO_27") (pin "1") (pinfunction "3_1") (pintype "passive"))
      (node (ref "R30") (pin "2") (pinfunction "2_2") (pintype "passive"))
    )
    (net (code "56") (name "Net-(IO_28-3)") (class "Default")
      (node (ref "IO_28") (pin "1") (pinfunction "3_1") (pintype "passive"))
      (node (ref "R31") (pin "2") (pinfunction "2_2") (pintype "passive"))
    )
    (net (code "57") (name "Net-(IO_29-3)") (class "Default")
      (node (ref "IO_29") (pin "1") (pinfunction "3_1") (pintype "passive"))
      (node (ref "R32") (pin "2") (pinfunction "2_2") (pintype "passive"))
    )
    (net (code "58") (name "Net-(IO_30-3)") (class "Default")
      (node (ref "IO_30") (pin "1") (pinfunction "3_1") (pintype "passive"))
      (node (ref "R33") (pin "2") (pinfunction "2_2") (pintype "passive"))
    )
    (net (code "59") (name "Net-(IO_31-3)") (class "Default")
      (node (ref "IO_31") (pin "1") (pinfunction "3_1") (pintype "passive"))
      (node (ref "R34") (pin "2") (pinfunction "2_2") (pintype "passive"))
    )
    (net (code "60") (name "Net-(IO_32-3)") (class "Default")
      (node (ref "IO_32") (pin "1") (pinfunction "3_1") (pintype "passive"))
      (node (ref "R35") (pin "2") (pinfunction "2_2") (pintype "passive"))
    )
    (net (code "61") (name "Net-(IO_33-3)") (class "Default")
      (node (ref "IO_33") (pin "1") (pinfunction "3_1") (pintype "passive"))
      (node (ref "R36") (pin "2") (pinfunction "2_2") (pintype "passive"))
    )
    (net (code "62") (name "Net-(IO_34-3)") (class "Default")
      (node (ref "IO_34") (pin "1") (pinfunction "3_1") (pintype "passive"))
      (node (ref "R37") (pin "2") (pinfunction "2_2") (pintype "passive"))
    )
    (net (code "63") (name "Net-(IO_35-3)") (class "Default")
      (node (ref "IO_35") (pin "1") (pinfunction "3_1") (pintype "passive"))
      (node (ref "R38") (pin "2") (pinfunction "2_2") (pintype "passive"))
    )
    (net (code "64") (name "Net-(IO_36-3)") (class "Default")
      (node (ref "IO_36") (pin "1") (pinfunction "3_1") (pintype "passive"))
      (node (ref "R39") (pin "2") (pinfunction "2_2") (pintype "passive"))
    )
    (net (code "65") (name "Net-(IO_37-3)") (class "Default")
      (node (ref "IO_37") (pin "1") (pinfunction "3_1") (pintype "passive"))
      (node (ref "R40") (pin "2") (pinfunction "2_2") (pintype "passive"))
    )
    (net (code "66") (name "Net-(IO_38-3)") (class "Default")
      (node (ref "IO_38") (pin "1") (pinfunction "3_1") (pintype "passive"))
      (node (ref "R41") (pin "2") (pinfunction "2_2") (pintype "passive"))
    )
    (net (code "67") (name "Net-(IO_39-3)") (class "Default")
      (node (ref "IO_39") (pin "1") (pinfunction "3_1") (pintype "passive"))
      (node (ref "R42") (pin "2") (pinfunction "2_2") (pintype "passive"))
    )
    (net (code "68") (name "Net-(MISO-3)") (class "Default")
      (node (ref "MISO") (pin "1") (pinfunction "3_1") (pintype "passive"))
      (node (ref "PIXI2_SDO") (pin "1") (pinfunction "3_1") (pintype "passive"))
      (node (ref "PIXI_SDO") (pin "1") (pinfunction "3_1") (pintype "passive"))
      (node (ref "TNSY_MISO") (pin "1") (pinfunction "3_1") (pintype "passive"))
    )
    (net (code "69") (name "Net-(MOSI-3)") (class "Default")
      (node (ref "MOSI") (pin "1") (pinfunction "3_1") (pintype "passive"))
      (node (ref "PIXI2_SDI") (pin "1") (pinfunction "3_1") (pintype "passive"))
      (node (ref "PIXI_SDI") (pin "1") (pinfunction "3_1") (pintype "passive"))
      (node (ref "TNSY_MOSI") (pin "1") (pinfunction "3_1") (pintype "passive"))
    )
    (net (code "70") (name "Net-(PIXI2_CS-3)") (class "Default")
      (node (ref "PIXI2_CS") (pin "1") (pinfunction "3_1") (pintype "passive"))
      (node (ref "PIXI2_CS_") (pin "1") (pinfunction "3_1") (pintype "passive"))
      (node (ref "TNSY_9") (pin "1") (pinfunction "3_1") (pintype "passive"))
    )
    (net (code "71") (name "Net-(PIXI2_SCK-3)") (class "Default")
      (node (ref "PIXI2_SCK") (pin "1") (pinfunction "3_1") (pintype "passive"))
      (node (ref "PIXI_SCK") (pin "1") (pinfunction "3_1") (pintype "passive"))
      (node (ref "SCK") (pin "1") (pinfunction "3_1") (pintype "passive"))
      (node (ref "TNSY_SCK") (pin "1") (pinfunction "3_1") (pintype "passive"))
    )
    (net (code "72") (name "Net-(PIXI_0-3)") (class "Default")
      (node (ref "PIXI_0") (pin "1") (pinfunction "3_1") (pintype "passive"))
      (node (ref "R1") (pin "1") (pinfunction "1_1") (pintype "passive"))
    )
    (net (code "73") (name "Net-(PIXI_1-3)") (class "Default")
      (node (ref "PIXI_1") (pin "1") (pinfunction "3_1") (pintype "passive"))
      (node (ref "R2") (pin "1") (pinfunction "1_1") (pintype "passive"))
    )
    (net (code "74") (name "Net-(PIXI_2-3)") (class "Default")
      (node (ref "PIXI_2") (pin "1") (pinfunction "3_1") (pintype "passive"))
      (node (ref "R3") (pin "1") (pinfunction "1_1") (pintype "passive"))
    )
    (net (code "75") (name "Net-(PIXI_3-3)") (class "Default")
      (node (ref "PIXI_3") (pin "1") (pinfunction "3_1") (pintype "passive"))
      (node (ref "R4") (pin "1") (pinfunction "1_1") (pintype "passive"))
    )
    (net (code "76") (name "Net-(PIXI_4-3)") (class "Default")
      (node (ref "PIXI_4") (pin "1") (pinfunction "3_1") (pintype "passive"))
      (node (ref "R5") (pin "1") (pinfunction "1_1") (pintype "passive"))
    )
    (net (code "77") (name "Net-(PIXI_5-3)") (class "Default")
      (node (ref "PIXI_5") (pin "1") (pinfunction "3_1") (pintype "passive"))
      (node (ref "R6") (pin "1") (pinfunction "1_1") (pintype "passive"))
    )
    (net (code "78") (name "Net-(PIXI_6-3)") (class "Default")
      (node (ref "PIXI_6") (pin "1") (pinfunction "3_1") (pintype "passive"))
      (node (ref "R7") (pin "1") (pinfunction "1_1") (pintype "passive"))
    )
    (net (code "79") (name "Net-(PIXI_7-3)") (class "Default")
      (node (ref "PIXI_7") (pin "1") (pinfunction "3_1") (pintype "passive"))
      (node (ref "R8") (pin "1") (pinfunction "1_1") (pintype "passive"))
    )
    (net (code "80") (name "Net-(PIXI_8-3)") (class "Default")
      (node (ref "PIXI_8") (pin "1") (pinfunction "3_1") (pintype "passive"))
      (node (ref "R9") (pin "1") (pinfunction "1_1") (pintype "passive"))
    )
    (net (code "81") (name "Net-(PIXI_9-3)") (class "Default")
      (node (ref "PIXI_9") (pin "1") (pinfunction "3_1") (pintype "passive"))
      (node (ref "R10") (pin "1") (pinfunction "1_1") (pintype "passive"))
    )
    (net (code "82") (name "Net-(PIXI_10-3)") (class "Default")
      (node (ref "PIXI_10") (pin "1") (pinfunction "3_1") (pintype "passive"))
      (node (ref "R11") (pin "1") (pinfunction "1_1") (pintype "passive"))
    )
    (net (code "83") (name "Net-(PIXI_11-3)") (class "Default")
      (node (ref "PIXI_11") (pin "1") (pinfunction "3_1") (pintype "passive"))
      (node (ref "R12") (pin "1") (pinfunction "1_1") (pintype "passive"))
    )
    (net (code "84") (name "Net-(PIXI_12-3)") (class "Default")
      (node (ref "PIXI_12") (pin "1") (pinfunction "3_1") (pintype "passive"))
      (node (ref "R13") (pin "1") (pinfunction "1_1") (pintype "passive"))
    )
    (net (code "85") (name "Net-(PIXI_13-3)") (class "Default")
      (node (ref "PIXI_13") (pin "1") (pinfunction "3_1") (pintype "passive"))
      (node (ref "R14") (pin "1") (pinfunction "1_1") (pintype "passive"))
    )
    (net (code "86") (name "Net-(PIXI_14-3)") (class "Default")
      (node (ref "PIXI_14") (pin "1") (pinfunction "3_1") (pintype "passive"))
      (node (ref "R15") (pin "1") (pinfunction "1_1") (pintype "passive"))
    )
    (net (code "87") (name "Net-(PIXI_15-3)") (class "Default")
      (node (ref "PIXI_15") (pin "1") (pinfunction "3_1") (pintype "passive"))
      (node (ref "R16") (pin "1") (pinfunction "1_1") (pintype "passive"))
    )
    (net (code "88") (name "Net-(PIXI_16-3)") (class "Default")
      (node (ref "PIXI_16") (pin "1") (pinfunction "3_1") (pintype "passive"))
      (node (ref "R17") (pin "1") (pinfunction "1_1") (pintype "passive"))
    )
    (net (code "89") (name "Net-(PIXI_17-3)") (class "Default")
      (node (ref "PIXI_17") (pin "1") (pinfunction "3_1") (pintype "passive"))
      (node (ref "R18") (pin "1") (pinfunction "1_1") (pintype "passive"))
    )
    (net (code "90") (name "Net-(PIXI_18-3)") (class "Default")
      (node (ref "PIXI_18") (pin "1") (pinfunction "3_1") (pintype "passive"))
      (node (ref "R19") (pin "1") (pinfunction "1_1") (pintype "passive"))
    )
    (net (code "91") (name "Net-(PIXI_19-3)") (class "Default")
      (node (ref "PIXI_19") (pin "1") (pinfunction "3_1") (pintype "passive"))
      (node (ref "R20") (pin "1") (pinfunction "1_1") (pintype "passive"))
    )
    (net (code "92") (name "Net-(PIXI_20-3)") (class "Default")
      (node (ref "PIXI_20") (pin "1") (pinfunction "3_1") (pintype "passive"))
      (node (ref "R23") (pin "1") (pinfunction "1_1") (pintype "passive"))
    )
    (net (code "93") (name "Net-(PIXI_21-3)") (class "Default")
      (node (ref "PIXI_21") (pin "1") (pinfunction "3_1") (pintype "passive"))
      (node (ref "R24") (pin "1") (pinfunction "1_1") (pintype "passive"))
    )
    (net (code "94") (name "Net-(PIXI_22-3)") (class "Default")
      (node (ref "PIXI_22") (pin "1") (pinfunction "3_1") (pintype "passive"))
      (node (ref "R25") (pin "1") (pinfunction "1_1") (pintype "passive"))
    )
    (net (code "95") (name "Net-(PIXI_23-3)") (class "Default")
      (node (ref "PIXI_23") (pin "1") (pinfunction "3_1") (pintype "passive"))
      (node (ref "R26") (pin "1") (pinfunction "1_1") (pintype "passive"))
    )
    (net (code "96") (name "Net-(PIXI_24-3)") (class "Default")
      (node (ref "PIXI_24") (pin "1") (pinfunction "3_1") (pintype "passive"))
      (node (ref "R27") (pin "1") (pinfunction "1_1") (pintype "passive"))
    )
    (net (code "97") (name "Net-(PIXI_25-3)") (class "Default")
      (node (ref "PIXI_25") (pin "1") (pinfunction "3_1") (pintype "passive"))
      (node (ref "R28") (pin "1") (pinfunction "1_1") (pintype "passive"))
    )
    (net (code "98") (name "Net-(PIXI_26-3)") (class "Default")
      (node (ref "PIXI_26") (pin "1") (pinfunction "3_1") (pintype "passive"))
      (node (ref "R29") (pin "1") (pinfunction "1_1") (pintype "passive"))
    )
    (net (code "99") (name "Net-(PIXI_27-3)") (class "Default")
      (node (ref "PIXI_27") (pin "1") (pinfunction "3_1") (pintype "passive"))
      (node (ref "R30") (pin "1") (pinfunction "1_1") (pintype "passive"))
    )
    (net (code "100") (name "Net-(PIXI_28-3)") (class "Default")
      (node (ref "PIXI_28") (pin "1") (pinfunction "3_1") (pintype "passive"))
      (node (ref "R31") (pin "1") (pinfunction "1_1") (pintype "passive"))
    )
    (net (code "101") (name "Net-(PIXI_29-3)") (class "Default")
      (node (ref "PIXI_29") (pin "1") (pinfunction "3_1") (pintype "passive"))
      (node (ref "R32") (pin "1") (pinfunction "1_1") (pintype "passive"))
    )
    (net (code "102") (name "Net-(PIXI_30-3)") (class "Default")
      (node (ref "PIXI_30") (pin "1") (pinfunction "3_1") (pintype "passive"))
      (node (ref "R33") (pin "1") (pinfunction "1_1") (pintype "passive"))
    )
    (net (code "103") (name "Net-(PIXI_31-3)") (class "Default")
      (node (ref "PIXI_31") (pin "1") (pinfunction "3_1") (pintype "passive"))
      (node (ref "R34") (pin "1") (pinfunction "1_1") (pintype "passive"))
    )
    (net (code "104") (name "Net-(PIXI_32-3)") (class "Default")
      (node (ref "PIXI_32") (pin "1") (pinfunction "3_1") (pintype "passive"))
      (node (ref "R35") (pin "1") (pinfunction "1_1") (pintype "passive"))
    )
    (net (code "105") (name "Net-(PIXI_33-3)") (class "Default")
      (node (ref "PIXI_33") (pin "1") (pinfunction "3_1") (pintype "passive"))
      (node (ref "R36") (pin "1") (pinfunction "1_1") (pintype "passive"))
    )
    (net (code "106") (name "Net-(PIXI_34-3)") (class "Default")
      (node (ref "PIXI_34") (pin "1") (pinfunction "3_1") (pintype "passive"))
      (node (ref "R37") (pin "1") (pinfunction "1_1") (pintype "passive"))
    )
    (net (code "107") (name "Net-(PIXI_35-3)") (class "Default")
      (node (ref "PIXI_35") (pin "1") (pinfunction "3_1") (pintype "passive"))
      (node (ref "R38") (pin "1") (pinfunction "1_1") (pintype "passive"))
    )
    (net (code "108") (name "Net-(PIXI_36-3)") (class "Default")
      (node (ref "PIXI_36") (pin "1") (pinfunction "3_1") (pintype "passive"))
      (node (ref "R39") (pin "1") (pinfunction "1_1") (pintype "passive"))
    )
    (net (code "109") (name "Net-(PIXI_37-3)") (class "Default")
      (node (ref "PIXI_37") (pin "1") (pinfunction "3_1") (pintype "passive"))
      (node (ref "R40") (pin "1") (pinfunction "1_1") (pintype "passive"))
    )
    (net (code "110") (name "Net-(PIXI_38-3)") (class "Default")
      (node (ref "PIXI_38") (pin "1") (pinfunction "3_1") (pintype "passive"))
      (node (ref "R41") (pin "1") (pinfunction "1_1") (pintype "passive"))
    )
    (net (code "111") (name "Net-(PIXI_39-3)") (class "Default")
      (node (ref "PIXI_39") (pin "1") (pinfunction "3_1") (pintype "passive"))
      (node (ref "R42") (pin "1") (pinfunction "1_1") (pintype "passive"))
    )
    (net (code "112") (name "Net-(PIXI_CS-3)") (class "Default")
      (node (ref "PIXI_CS") (pin "1") (pinfunction "3_1") (pintype "passive"))
      (node (ref "TNSY_CS") (pin "1") (pinfunction "3_1") (pintype "passive"))
    )
    (net (code "113") (name "unconnected-(PIXI1_CS_-3-Pad1)") (class "Default")
      (node (ref "PIXI1_CS_") (pin "1") (pinfunction "3_1") (pintype "passive"))
    )
    (net (code "114") (name "unconnected-(PIXI2_INT-3-Pad1)") (class "Default")
      (node (ref "PIXI2_INT") (pin "1") (pinfunction "3_1") (pintype "passive"))
    )
    (net (code "115") (name "unconnected-(PIXI2_NC1-3-Pad1)") (class "Default")
      (node (ref "PIXI2_NC1") (pin "1") (pinfunction "3_1") (pintype "passive"))
    )
    (net (code "116") (name "unconnected-(PIXI2_NC2-3-Pad1)") (class "Default")
      (node (ref "PIXI2_NC2") (pin "1") (pinfunction "3_1") (pintype "passive"))
    )
    (net (code "117") (name "unconnected-(PIXI2_NC3-3-Pad1)") (class "Default")
      (node (ref "PIXI2_NC3") (pin "1") (pinfunction "3_1") (pintype "passive"))
    )
    (net (code "118") (name "unconnected-(PIXI2_NC4-3-Pad1)") (class "Default")
      (node (ref "PIXI2_NC4") (pin "1") (pinfunction "3_1") (pintype "passive"))
    )
    (net (code "119") (name "unconnected-(PIXI2_NC5-3-Pad1)") (class "Default")
      (node (ref "PIXI2_NC5") (pin "1") (pinfunction "3_1") (pintype "passive"))
    )
    (net (code "120") (name "unconnected-(PIXI2_NC6-3-Pad1)") (class "Default")
      (node (ref "PIXI2_NC6") (pin "1") (pinfunction "3_1") (pintype "passive"))
    )
    (net (code "121") (name "unconnected-(PIXI_INT-3-Pad1)") (class "Default")
      (node (ref "PIXI_INT") (pin "1") (pinfunction "3_1") (pintype "passive"))
    )
    (net (code "122") (name "unconnected-(PIXI_NC1-3-Pad1)") (class "Default")
      (node (ref "PIXI_NC1") (pin "1") (pinfunction "3_1") (pintype "passive"))
    )
    (net (code "123") (name "unconnected-(PIXI_NC2-3-Pad1)") (class "Default")
      (node (ref "PIXI_NC2") (pin "1") (pinfunction "3_1") (pintype "passive"))
    )
    (net (code "124") (name "unconnected-(PIXI_NC3-3-Pad1)") (class "Default")
      (node (ref "PIXI_NC3") (pin "1") (pinfunction "3_1") (pintype "passive"))
    )
    (net (code "125") (name "unconnected-(PIXI_NC4-3-Pad1)") (class "Default")
      (node (ref "PIXI_NC4") (pin "1") (pinfunction "3_1") (pintype "passive"))
    )
    (net (code "126") (name "unconnected-(PIXI_NC5-3-Pad1)") (class "Default")
      (node (ref "PIXI_NC5") (pin "1") (pinfunction "3_1") (pintype "passive"))
    )
    (net (code "127") (name "unconnected-(PIXI_NC6-3-Pad1)") (class "Default")
      (node (ref "PIXI_NC6") (pin "1") (pinfunction "3_1") (pintype "passive"))
    )
    (net (code "128") (name "unconnected-(TNSY_GND2-3-Pad1)") (class "Default")
      (node (ref "TNSY_GND2") (pin "1") (pinfunction "3_1") (pintype "passive"))
    )
  )
)
